# ProPrj_STM32F405RGT6__2024-12-01.net
KiCad netlist of a schematic drawn in EasyEDA Pro
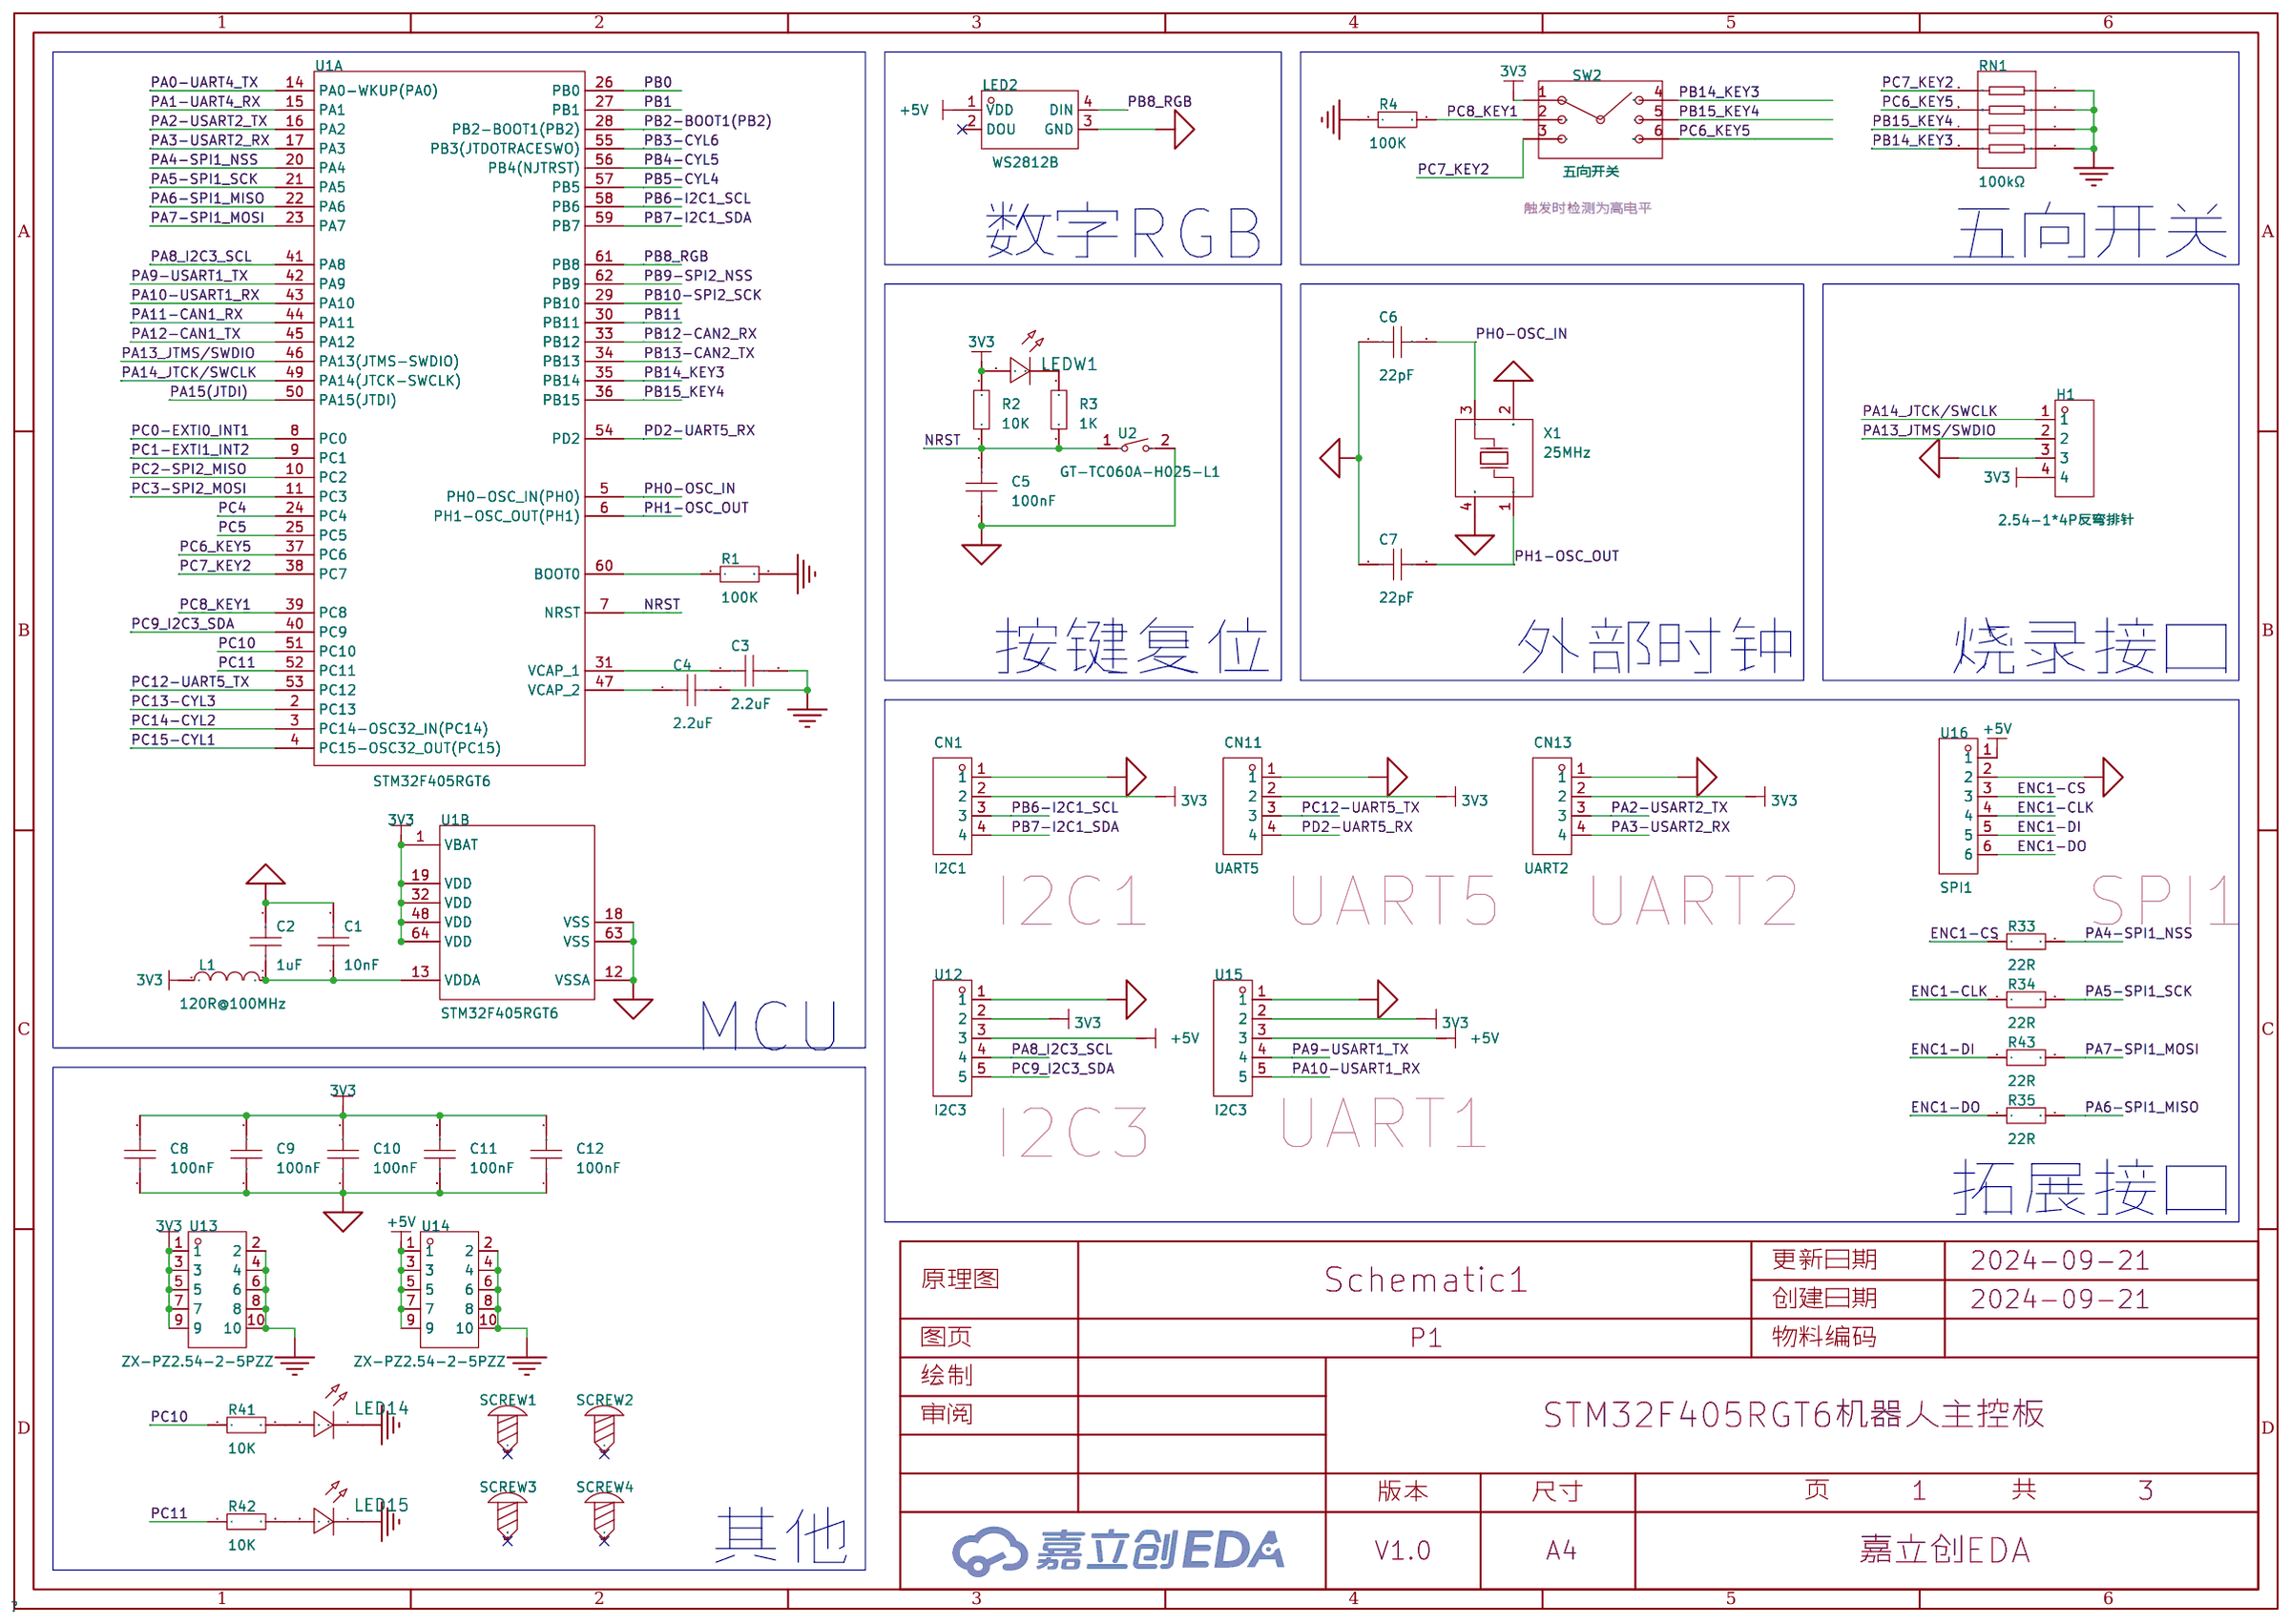
[diagram p0: P1]
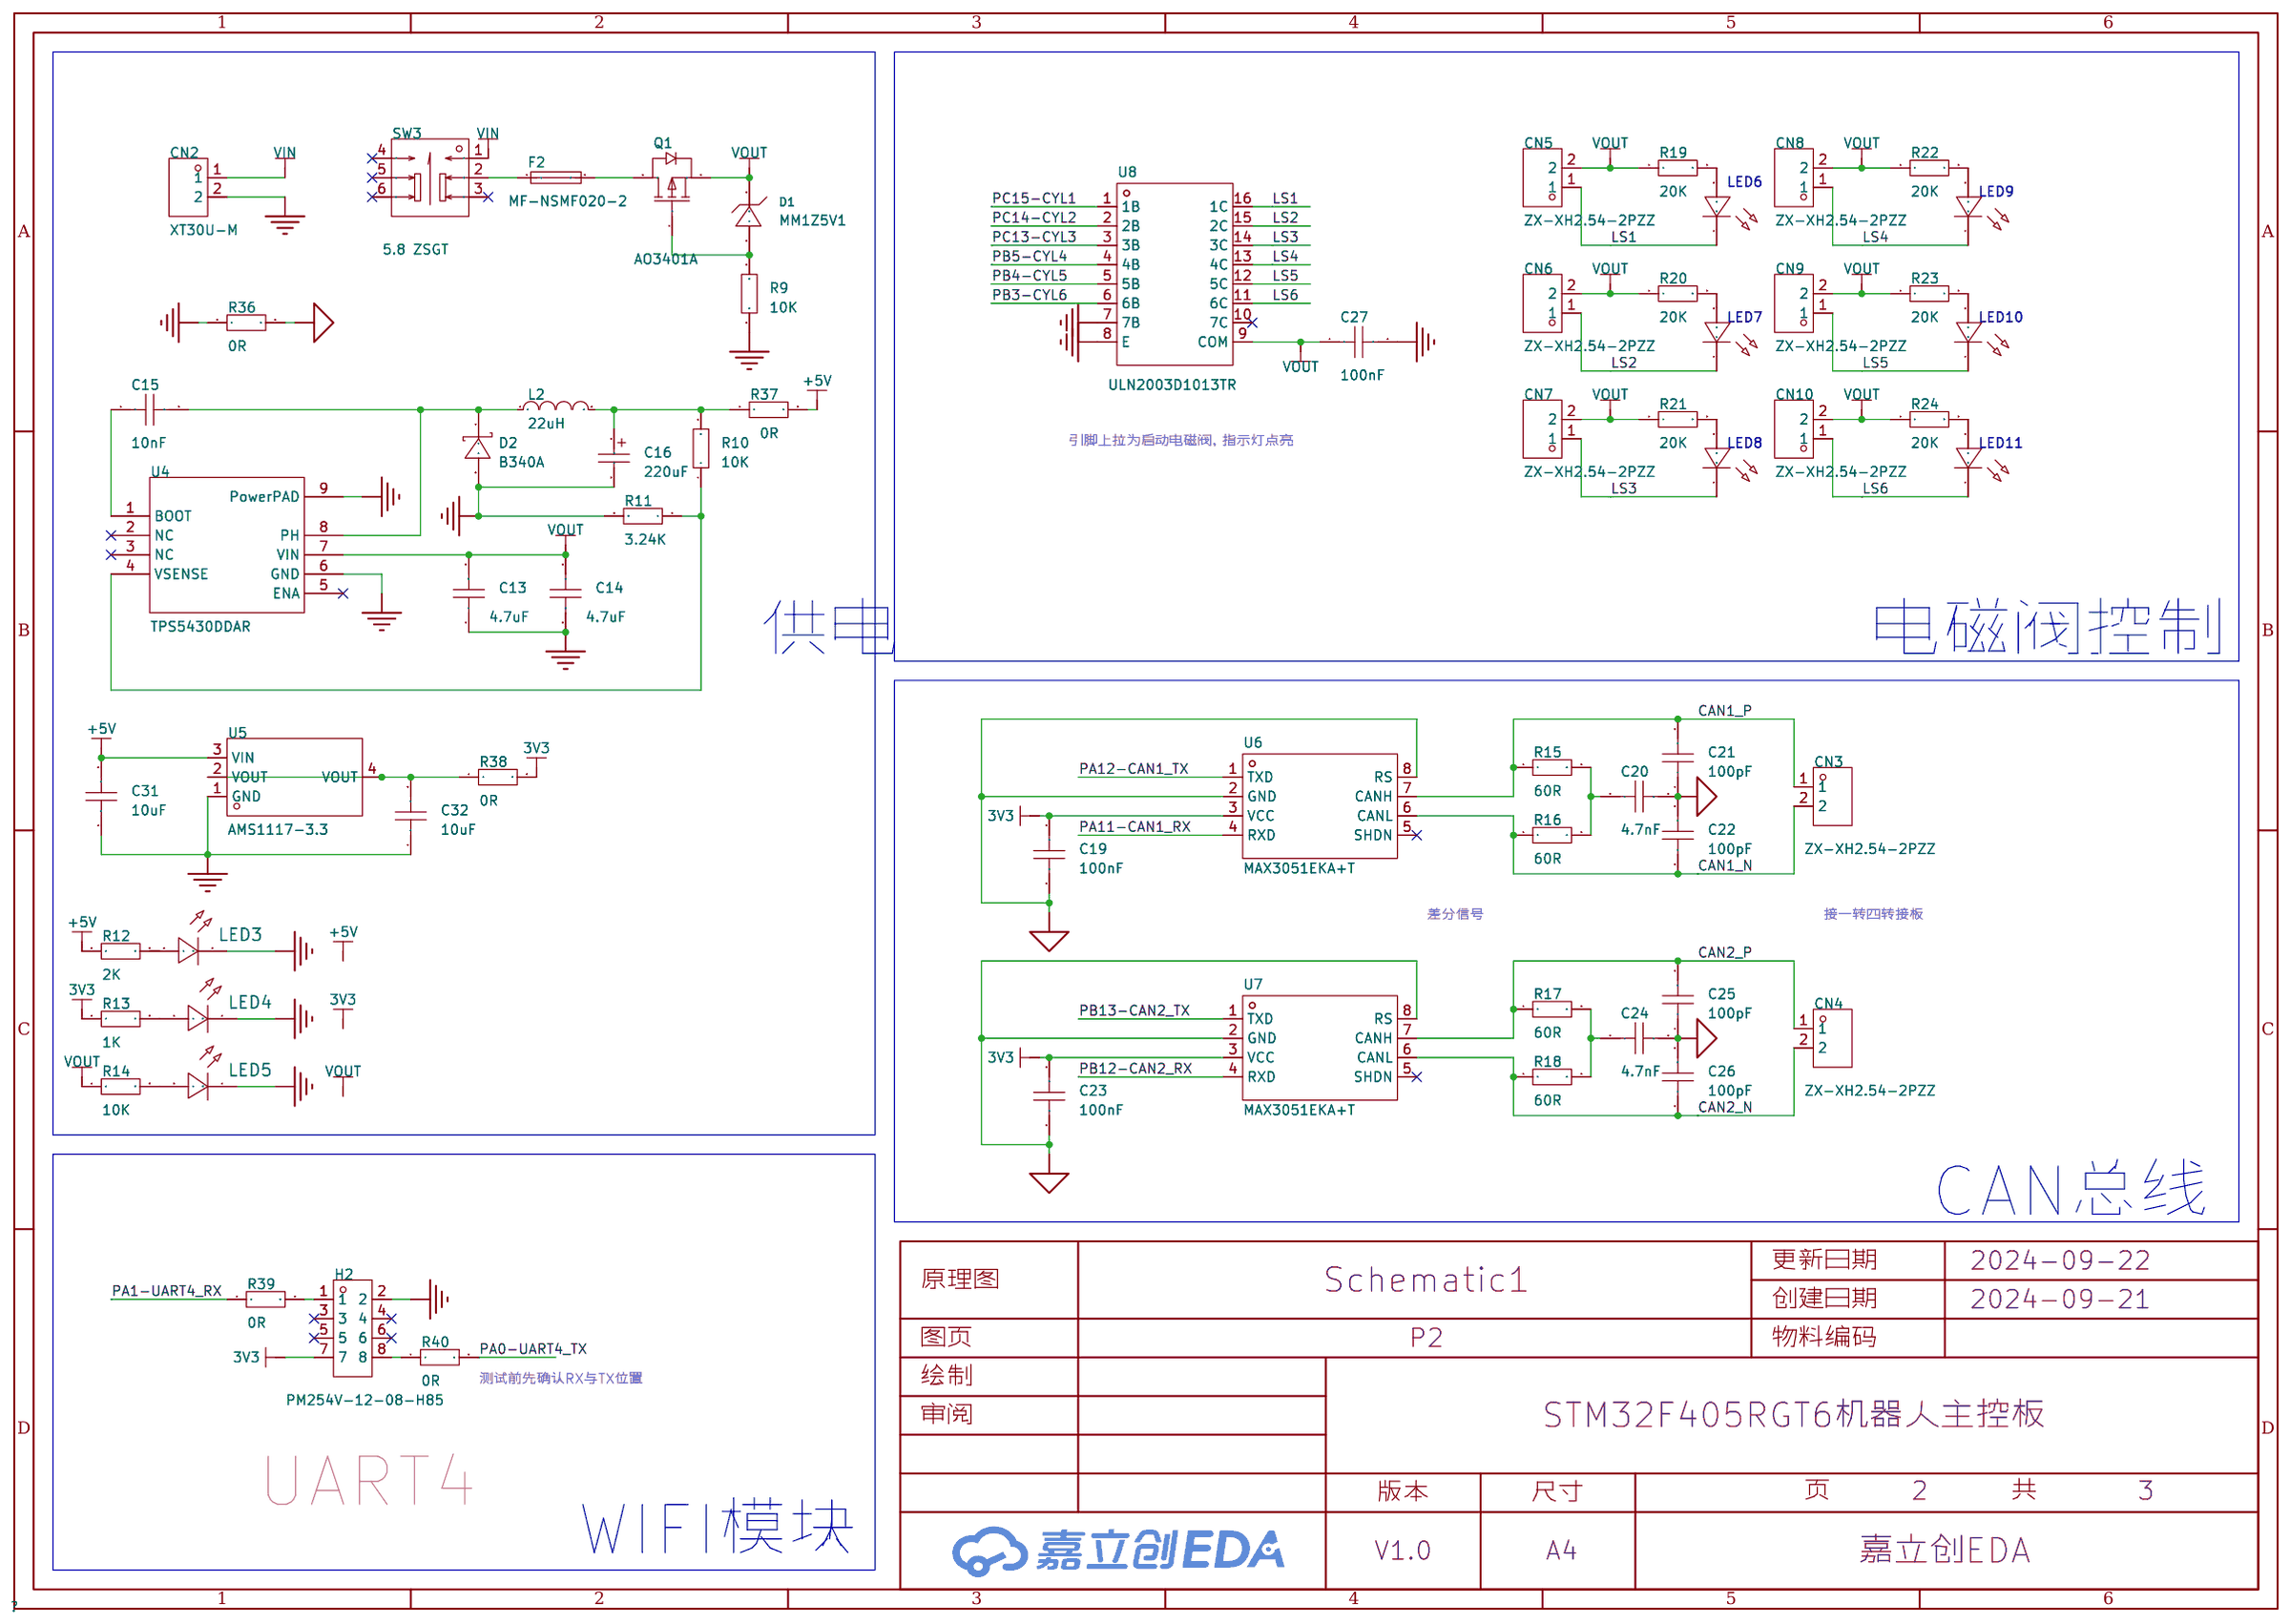
[diagram p1: P2]
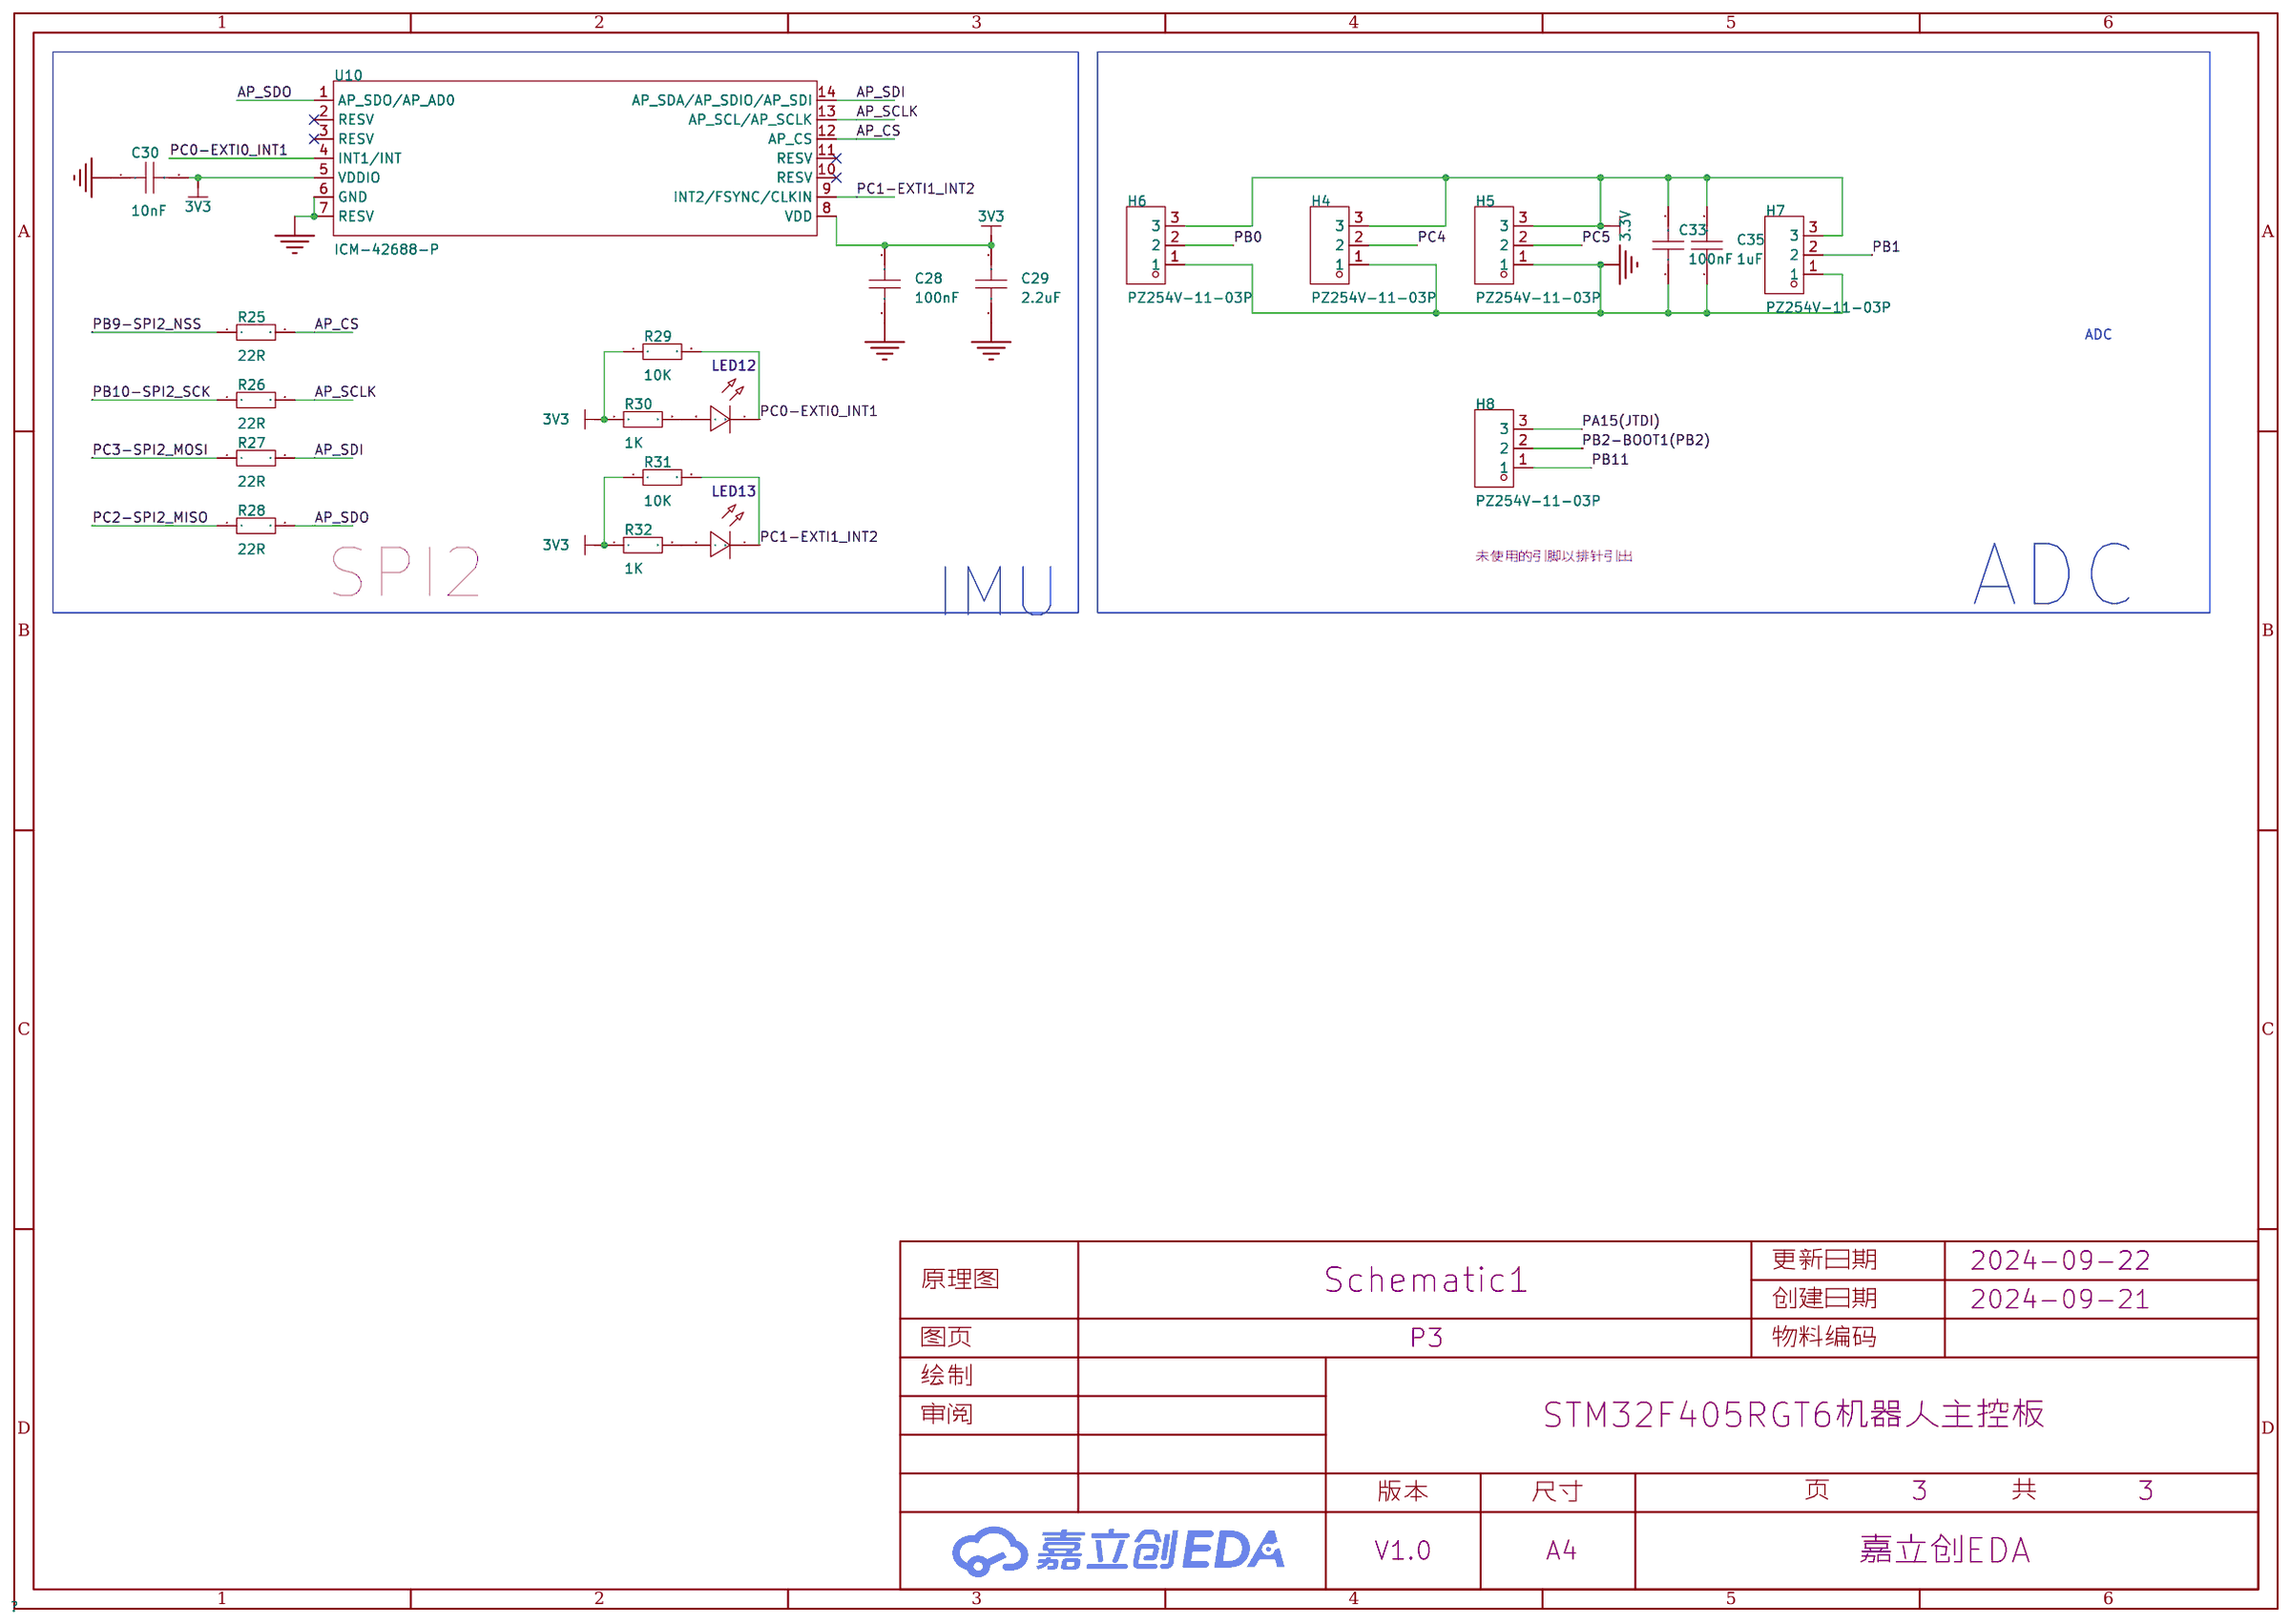
[diagram p2: P3]

(export (version "E")
  (design (tool "Eeschema 10.0.6"))
  (components
    (comp (ref "C1")
      (value "10nF")
      (footprint "easyedapro:C1206")
      (libsource (lib "easyedapro") (part "CapAcitance"))
    )
    (comp (ref "C2")
      (value "1uF")
      (footprint "easyedapro:C1206")
      (libsource (lib "easyedapro") (part "CapAcitance"))
    )
    (comp (ref "C3")
      (value "2.2uF")
      (footprint "easyedapro:C1206")
      (libsource (lib "easyedapro") (part "CapAcitance"))
    )
    (comp (ref "C4")
      (value "2.2uF")
      (footprint "easyedapro:C1206")
      (libsource (lib "easyedapro") (part "CapAcitance"))
    )
    (comp (ref "C5")
      (value "100nF")
      (footprint "easyedapro:C1206")
      (libsource (lib "easyedapro") (part "CapAcitance"))
    )
    (comp (ref "C6")
      (value "22pF")
      (footprint "easyedapro:C1206")
      (libsource (lib "easyedapro") (part "CapAcitance"))
    )
    (comp (ref "C7")
      (value "22pF")
      (footprint "easyedapro:C1206")
      (libsource (lib "easyedapro") (part "CapAcitance"))
    )
    (comp (ref "C8")
      (value "100nF")
      (footprint "easyedapro:C1206")
      (libsource (lib "easyedapro") (part "CapAcitance"))
    )
    (comp (ref "C9")
      (value "100nF")
      (footprint "easyedapro:C1206")
      (libsource (lib "easyedapro") (part "CapAcitance"))
    )
    (comp (ref "C10")
      (value "100nF")
      (footprint "easyedapro:C1206")
      (libsource (lib "easyedapro") (part "CapAcitance"))
    )
    (comp (ref "C11")
      (value "100nF")
      (footprint "easyedapro:C1206")
      (libsource (lib "easyedapro") (part "CapAcitance"))
    )
    (comp (ref "C12")
      (value "100nF")
      (footprint "easyedapro:C1206")
      (libsource (lib "easyedapro") (part "CapAcitance"))
    )
    (comp (ref "CN1")
      (value "I2C1")
      (footprint "easyedapro:CONN-TH_4P-P2.50_4PIN")
      (fields (field (name "Manufacturer") "Megastar(兆星)"))
      (libsource (lib "easyedapro") (part "ZX-XH2.54-4PZZ"))
    )
    (comp (ref "CN11")
      (value "UART5")
      (footprint "easyedapro:CONN-TH_4P-P2.50_4PIN")
      (fields (field (name "Manufacturer") "Megastar(兆星)"))
      (libsource (lib "easyedapro") (part "ZX-XH2.54-4PZZ"))
    )
    (comp (ref "CN13")
      (value "UART2")
      (footprint "easyedapro:CONN-TH_4P-P2.50_4PIN")
      (fields (field (name "Manufacturer") "Megastar(兆星)"))
      (libsource (lib "easyedapro") (part "ZX-XH2.54-4PZZ"))
    )
    (comp (ref "H1")
      (value "2.54-1*4P反弯排针")
      (footprint "easyedapro:HDR-TH_4P-P2.54-H-M-W10.4")
      (fields (field (name "Manufacturer") "BOOMELE(博穆精密)"))
      (libsource (lib "easyedapro") (part "2.54-1*4P反弯排针"))
    )
    (comp (ref "L1")
      (value "120R@100MHz")
      (footprint "easyedapro:L0603")
      (description "标称阻抗@测试频率:120Ω@100MHz;误差:±25%;直流电阻(RDC):50mΩ;")
      (fields (field (name "Manufacturer") "muRata(村田)"))
      (libsource (lib "easyedapro") (part "BLM18PG121SN1D_C14709"))
    )
    (comp (ref "LED2")
      (value "WS2812B")
      (footprint "easyedapro:LED-SMD_4P-L5.0-W5.0-BL_XL-5050RGBC")
      (description "5050七彩幻彩透明贴片LED灯珠 5050 幻彩透明四脚 ws2812B 内置驱动IC")
      (fields (field (name "Manufacturer") "XINGLIGHT(成兴光)"))
      (libsource (lib "easyedapro") (part "XL-5050RGBC-WS2812B"))
    )
    (comp (ref "LED14")
      (value "~")
      (footprint "easyedapro:LED_0603")
      (libsource (lib "easyedapro") (part "LED_R"))
    )
    (comp (ref "LED15")
      (value "~")
      (footprint "easyedapro:LED_0603")
      (libsource (lib "easyedapro") (part "LED_R"))
    )
    (comp (ref "LEDW1")
      (value "~")
      (footprint "easyedapro:LED_0603")
      (libsource (lib "easyedapro") (part "LED_R"))
    )
    (comp (ref "R1") (value "100K") (footprint "easyedapro:R0603") (libsource (lib "easyedapro") (part "电阻")))
    (comp (ref "R2") (value "10K") (footprint "easyedapro:R0603") (libsource (lib "easyedapro") (part "电阻")))
    (comp (ref "R3") (value "1K") (footprint "easyedapro:R0603") (libsource (lib "easyedapro") (part "电阻")))
    (comp (ref "R4") (value "100K") (footprint "easyedapro:R0603") (libsource (lib "easyedapro") (part "电阻")))
    (comp (ref "R33") (value "22R") (footprint "easyedapro:R0603") (libsource (lib "easyedapro") (part "电阻")))
    (comp (ref "R34") (value "22R") (footprint "easyedapro:R0603") (libsource (lib "easyedapro") (part "电阻")))
    (comp (ref "R35") (value "22R") (footprint "easyedapro:R0603") (libsource (lib "easyedapro") (part "电阻")))
    (comp (ref "R41") (value "10K") (footprint "easyedapro:R0603") (libsource (lib "easyedapro") (part "电阻")))
    (comp (ref "R42") (value "10K") (footprint "easyedapro:R0603") (libsource (lib "easyedapro") (part "电阻")))
    (comp (ref "R43") (value "22R") (footprint "easyedapro:R0603") (libsource (lib "easyedapro") (part "电阻")))
    (comp (ref "RN1")
      (value "100kΩ")
      (footprint "easyedapro:RES-ARRAY-SMD_0603-8P-L3.2-W1.6-BL")
      (description "电阻器数:4;阻值:100kΩ;精度:±1%;单个元件功率:62.5mW;温度系数:±200ppm/°C;")
      (fields
        (field (name "Manufacturer Part") "4D03WGF1003T5E")
        (field (name "Manufacturer") "UNI-ROYAL(厚声)")
      )
      (libsource (lib "easyedapro") (part "4D03WGF1003T5E"))
    )
    (comp (ref "SCREW1")
      (value "~")
      (footprint "easyedapro:M3螺丝")
      (libsource (lib "easyedapro") (part "螺丝孔"))
    )
    (comp (ref "SCREW2")
      (value "~")
      (footprint "easyedapro:M3螺丝")
      (libsource (lib "easyedapro") (part "螺丝孔"))
    )
    (comp (ref "SCREW3")
      (value "~")
      (footprint "easyedapro:M3螺丝")
      (libsource (lib "easyedapro") (part "螺丝孔"))
    )
    (comp (ref "SCREW4")
      (value "~")
      (footprint "easyedapro:M3螺丝")
      (libsource (lib "easyedapro") (part "螺丝孔"))
    )
    (comp (ref "SW2")
      (value "五向开关")
      (footprint "easyedapro:SW-SMD_K1-1504SA-06")
      (fields (field (name "Manufacturer") "韩国韩荣"))
      (libsource (lib "easyedapro") (part "K1-1504SA-06"))
    )
    (comp (ref "U1")
      (value "STM32F405RGT6")
      (footprint "easyedapro:LQFP-64_L10.0-W10.0-P0.50-LS12.0-BL")
      (description "CPU内核:ARM-M4;程序存储容量:1MB;RAM总容量:192KB;GPIO端口数量:51;工作电压范围:1.8V~3.6V;CPU最大主频:168MHz;程序存储器类型:FLASH;")
      (fields (field (name "Manufacturer") "ST(意法半导体)"))
      (libsource (lib "easyedapro") (part "STM32F405RGT6"))
    )
    (comp (ref "U2")
      (value "GT-TC060A-H025-L1")
      (footprint "easyedapro:SW-SMD_L6.1-W3.5-LS8.0")
      (fields (field (name "Manufacturer") "G-Switch(品赞)"))
      (libsource (lib "easyedapro") (part "GT-TC060A-H025-L1"))
    )
    (comp (ref "U12")
      (value "I2C3")
      (footprint "easyedapro:CONN-TH_5P-P2.50_ZX-XH2.54-5PZZ")
      (fields (field (name "Manufacturer") "Megastar(兆星)"))
      (libsource (lib "easyedapro") (part "ZX-XH2.54-5PZZ"))
    )
    (comp (ref "U13")
      (value "ZX-PZ2.54-2-5PZZ")
      (footprint "easyedapro:HDR-TH_10P-P2.54-V-M-R2-C5-S2.54")
      (fields (field (name "Manufacturer") "Megastar(兆星)"))
      (libsource (lib "easyedapro") (part "ZX-PZ2.54-2-5PZZ"))
    )
    (comp (ref "U14")
      (value "ZX-PZ2.54-2-5PZZ")
      (footprint "easyedapro:HDR-TH_10P-P2.54-V-M-R2-C5-S2.54")
      (fields (field (name "Manufacturer") "Megastar(兆星)"))
      (libsource (lib "easyedapro") (part "ZX-PZ2.54-2-5PZZ"))
    )
    (comp (ref "U15")
      (value "I2C3")
      (footprint "easyedapro:CONN-TH_5P-P2.50_ZX-XH2.54-5PZZ")
      (fields (field (name "Manufacturer") "Megastar(兆星)"))
      (libsource (lib "easyedapro") (part "ZX-XH2.54-5PZZ"))
    )
    (comp (ref "U16")
      (value "SPI1")
      (footprint "easyedapro:CONN-TH_6P-P2.50_ZX-XH2.54-6PZZ")
      (fields (field (name "Manufacturer") "Megastar(兆星)"))
      (libsource (lib "easyedapro") (part "ZX-XH2.54-6PZZ"))
    )
    (comp (ref "X1")
      (value "25MHz")
      (footprint "easyedapro:OSC-SMD_4P-L3.2-W2.5-BL")
      (description "晶振类型:贴片晶振;频率:25MHz;常温频差:±10ppm;外接负载电容:20pF;频率稳定度(全温):±20ppm;")
      (fields (field (name "Manufacturer Part") "X322525MSB4SI") (field (name "Manufacturer") "YXC(扬兴晶振)"))
      (libsource (lib "easyedapro") (part "X322525MSB4SI"))
    )
    (comp (ref "C13")
      (value "4.7uF")
      (footprint "easyedapro:C1206")
      (libsource (lib "easyedapro") (part "CapAcitance"))
    )
    (comp (ref "C14")
      (value "4.7uF")
      (footprint "easyedapro:C1206")
      (libsource (lib "easyedapro") (part "CapAcitance"))
    )
    (comp (ref "C15")
      (value "10nF")
      (footprint "easyedapro:C1206")
      (libsource (lib "easyedapro") (part "CapAcitance"))
    )
    (comp (ref "C16")
      (value "220uF")
      (footprint "easyedapro:CASE-B_3528")
      (description "容值:220uF;精度:±20%;额定电压:6.3V;等效串联电阻:500mΩ@100kHz;")
      (fields
        (field (name "Manufacturer Part") "TLJB227M006R0500")
        (field (name "Manufacturer") "Kyocera AVX")
      )
      (libsource (lib "easyedapro") (part "TLJB227M006R0500"))
    )
    (comp (ref "C19")
      (value "100nF")
      (footprint "easyedapro:C1206")
      (libsource (lib "easyedapro") (part "CapAcitance"))
    )
    (comp (ref "C20")
      (value "4.7nF")
      (footprint "easyedapro:C1206")
      (libsource (lib "easyedapro") (part "CapAcitance"))
    )
    (comp (ref "C21")
      (value "100pF")
      (footprint "easyedapro:C1206")
      (libsource (lib "easyedapro") (part "CapAcitance"))
    )
    (comp (ref "C22")
      (value "100pF")
      (footprint "easyedapro:C1206")
      (libsource (lib "easyedapro") (part "CapAcitance"))
    )
    (comp (ref "C23")
      (value "100nF")
      (footprint "easyedapro:C1206")
      (libsource (lib "easyedapro") (part "CapAcitance"))
    )
    (comp (ref "C24")
      (value "4.7nF")
      (footprint "easyedapro:C1206")
      (libsource (lib "easyedapro") (part "CapAcitance"))
    )
    (comp (ref "C25")
      (value "100pF")
      (footprint "easyedapro:C1206")
      (libsource (lib "easyedapro") (part "CapAcitance"))
    )
    (comp (ref "C26")
      (value "100pF")
      (footprint "easyedapro:C1206")
      (libsource (lib "easyedapro") (part "CapAcitance"))
    )
    (comp (ref "C27")
      (value "100nF")
      (footprint "easyedapro:C1206")
      (libsource (lib "easyedapro") (part "CapAcitance"))
    )
    (comp (ref "C31")
      (value "10uF")
      (footprint "easyedapro:C1210")
      (description "容值:10uF;精度:±10%;额定电压:100V;材质(温度系数):X7R;")
      (fields (field (name "Manufacturer Part") "FS32X106K101EGG") (field (name "Manufacturer") "PSA(信昌电陶)"))
      (libsource (lib "easyedapro") (part "FS32X106K101EGG"))
    )
    (comp (ref "C32")
      (value "10uF")
      (footprint "easyedapro:C1210")
      (description "容值:10uF;精度:±10%;额定电压:100V;材质(温度系数):X7R;")
      (fields (field (name "Manufacturer Part") "FS32X106K101EGG") (field (name "Manufacturer") "PSA(信昌电陶)"))
      (libsource (lib "easyedapro") (part "FS32X106K101EGG"))
    )
    (comp (ref "CN2")
      (value "XT30U-M")
      (footprint "easyedapro:CONN-TH_XT30U-M")
      (description "类别:-;类型1:-;")
      (fields (field (name "Manufacturer") "AMASS(艾迈斯)"))
      (libsource (lib "easyedapro") (part "XT30U-M"))
    )
    (comp (ref "CN3")
      (value "ZX-XH2.54-2PZZ")
      (footprint "easyedapro:CONN-TH_2P-P2.50_HX25003-2A")
      (fields (field (name "Manufacturer") "Megastar(兆星)"))
      (libsource (lib "easyedapro") (part "ZX-XH2.54-2PZZ"))
    )
    (comp (ref "CN4")
      (value "ZX-XH2.54-2PZZ")
      (footprint "easyedapro:CONN-TH_2P-P2.50_HX25003-2A")
      (fields (field (name "Manufacturer") "Megastar(兆星)"))
      (libsource (lib "easyedapro") (part "ZX-XH2.54-2PZZ"))
    )
    (comp (ref "CN5")
      (value "ZX-XH2.54-2PZZ")
      (footprint "easyedapro:CONN-TH_2P-P2.50_HX25003-2A")
      (fields (field (name "Manufacturer") "Megastar(兆星)"))
      (libsource (lib "easyedapro") (part "ZX-XH2.54-2PZZ"))
    )
    (comp (ref "CN6")
      (value "ZX-XH2.54-2PZZ")
      (footprint "easyedapro:CONN-TH_2P-P2.50_HX25003-2A")
      (fields (field (name "Manufacturer") "Megastar(兆星)"))
      (libsource (lib "easyedapro") (part "ZX-XH2.54-2PZZ"))
    )
    (comp (ref "CN7")
      (value "ZX-XH2.54-2PZZ")
      (footprint "easyedapro:CONN-TH_2P-P2.50_HX25003-2A")
      (fields (field (name "Manufacturer") "Megastar(兆星)"))
      (libsource (lib "easyedapro") (part "ZX-XH2.54-2PZZ"))
    )
    (comp (ref "CN8")
      (value "ZX-XH2.54-2PZZ")
      (footprint "easyedapro:CONN-TH_2P-P2.50_HX25003-2A")
      (fields (field (name "Manufacturer") "Megastar(兆星)"))
      (libsource (lib "easyedapro") (part "ZX-XH2.54-2PZZ"))
    )
    (comp (ref "CN9")
      (value "ZX-XH2.54-2PZZ")
      (footprint "easyedapro:CONN-TH_2P-P2.50_HX25003-2A")
      (fields (field (name "Manufacturer") "Megastar(兆星)"))
      (libsource (lib "easyedapro") (part "ZX-XH2.54-2PZZ"))
    )
    (comp (ref "CN10")
      (value "ZX-XH2.54-2PZZ")
      (footprint "easyedapro:CONN-TH_2P-P2.50_HX25003-2A")
      (fields (field (name "Manufacturer") "Megastar(兆星)"))
      (libsource (lib "easyedapro") (part "ZX-XH2.54-2PZZ"))
    )
    (comp (ref "D1")
      (value "MM1Z5V1")
      (footprint "easyedapro:SOD-123_L2.8-W1.8-LS3.7-RD")
      (description "二极管配置:独立式;稳压值(标称值):5.1V;稳压值(范围):4.8V~5.4V;功率:500mW;精度:±6%;")
      (fields (field (name "Manufacturer") "晶导微电子"))
      (libsource (lib "easyedapro") (part "MM1Z5V1_C112534"))
    )
    (comp (ref "D2")
      (value "B340A")
      (footprint "easyedapro:SMA_L4.3-W2.6-LS5.1-RD")
      (description "二极管配置:独立式;正向压降(Vf):550mV@3A;直流反向耐压(Vr):40V;整流电流:3A;")
      (fields (field (name "Manufacturer") "MDD(辰达半导体)"))
      (libsource (lib "easyedapro") (part "B340A"))
    )
    (comp (ref "F2")
      (value "MF-NSMF020-2")
      (footprint "easyedapro:F1206")
      (description "最大电压:24V;最大电流:10A;保持电流:200mA;跳闸电流:460mA;")
      (fields (field (name "Manufacturer") "BOURNS"))
      (libsource (lib "easyedapro") (part "MF-NSMF020-2"))
    )
    (comp (ref "H2")
      (value "PM254V-12-08-H85")
      (footprint "easyedapro:HDR-TH_8P-P2.54-V-F-R2-C4-S2.54")
      (fields (field (name "Manufacturer") "XFCN(兴飞)"))
      (libsource (lib "easyedapro") (part "PM254V-12-08-H85_C2834799"))
    )
    (comp (ref "L2")
      (value "22uH")
      (footprint "easyedapro:IND-SMD_L4.0-W4.0_LQH44PN2R2MP0L")
      (description "电感值:22uH;精度:±20%;额定电流:-;饱和电流(Isat):1.05A;")
      (fields (field (name "Manufacturer Part") "SMNR4020-22UH") (field (name "Manufacturer") "SXN(顺翔诺)"))
      (libsource (lib "easyedapro") (part "SMNR4020-22UH"))
    )
    (comp (ref "LED3")
      (value "~")
      (footprint "easyedapro:LED_0603")
      (libsource (lib "easyedapro") (part "LED_R"))
    )
    (comp (ref "LED4")
      (value "~")
      (footprint "easyedapro:LED_0603")
      (libsource (lib "easyedapro") (part "LED_R"))
    )
    (comp (ref "LED5")
      (value "~")
      (footprint "easyedapro:LED_0603")
      (libsource (lib "easyedapro") (part "LED_R"))
    )
    (comp (ref "LED6")
      (value "~")
      (footprint "easyedapro:LED_0603")
      (libsource (lib "easyedapro") (part "LED_B"))
    )
    (comp (ref "LED7")
      (value "~")
      (footprint "easyedapro:LED_0603")
      (libsource (lib "easyedapro") (part "LED_B"))
    )
    (comp (ref "LED8")
      (value "~")
      (footprint "easyedapro:LED_0603")
      (libsource (lib "easyedapro") (part "LED_B"))
    )
    (comp (ref "LED9")
      (value "~")
      (footprint "easyedapro:LED_0603")
      (libsource (lib "easyedapro") (part "LED_B"))
    )
    (comp (ref "LED10")
      (value "~")
      (footprint "easyedapro:LED_0603")
      (libsource (lib "easyedapro") (part "LED_B"))
    )
    (comp (ref "LED11")
      (value "~")
      (footprint "easyedapro:LED_0603")
      (libsource (lib "easyedapro") (part "LED_B"))
    )
    (comp (ref "Q1")
      (value "AO3401A")
      (footprint "easyedapro:SOT-23_L2.9-W1.3-P1.90-LS2.4-BR")
      (fields (field (name "Manufacturer") "AOS"))
      (libsource (lib "easyedapro") (part "AO3401A"))
    )
    (comp (ref "R9") (value "10K") (footprint "easyedapro:R0603") (libsource (lib "easyedapro") (part "电阻")))
    (comp (ref "R10") (value "10K") (footprint "easyedapro:R0603") (libsource (lib "easyedapro") (part "电阻")))
    (comp (ref "R11")
      (value "3.24K")
      (footprint "easyedapro:R0603")
      (libsource (lib "easyedapro") (part "电阻"))
    )
    (comp (ref "R12") (value "2K") (footprint "easyedapro:R0603") (libsource (lib "easyedapro") (part "电阻")))
    (comp (ref "R13") (value "1K") (footprint "easyedapro:R0603") (libsource (lib "easyedapro") (part "电阻")))
    (comp (ref "R14") (value "10K") (footprint "easyedapro:R0603") (libsource (lib "easyedapro") (part "电阻")))
    (comp (ref "R15") (value "60R") (footprint "easyedapro:R0603") (libsource (lib "easyedapro") (part "电阻")))
    (comp (ref "R16") (value "60R") (footprint "easyedapro:R0603") (libsource (lib "easyedapro") (part "电阻")))
    (comp (ref "R17") (value "60R") (footprint "easyedapro:R0603") (libsource (lib "easyedapro") (part "电阻")))
    (comp (ref "R18") (value "60R") (footprint "easyedapro:R0603") (libsource (lib "easyedapro") (part "电阻")))
    (comp (ref "R19") (value "20K") (footprint "easyedapro:R0603") (libsource (lib "easyedapro") (part "电阻")))
    (comp (ref "R20") (value "20K") (footprint "easyedapro:R0603") (libsource (lib "easyedapro") (part "电阻")))
    (comp (ref "R21") (value "20K") (footprint "easyedapro:R0603") (libsource (lib "easyedapro") (part "电阻")))
    (comp (ref "R22") (value "20K") (footprint "easyedapro:R0603") (libsource (lib "easyedapro") (part "电阻")))
    (comp (ref "R23") (value "20K") (footprint "easyedapro:R0603") (libsource (lib "easyedapro") (part "电阻")))
    (comp (ref "R24") (value "20K") (footprint "easyedapro:R0603") (libsource (lib "easyedapro") (part "电阻")))
    (comp (ref "R36") (value "0R") (footprint "easyedapro:R0603") (libsource (lib "easyedapro") (part "电阻")))
    (comp (ref "R37") (value "0R") (footprint "easyedapro:R0603") (libsource (lib "easyedapro") (part "电阻")))
    (comp (ref "R38") (value "0R") (footprint "easyedapro:R0603") (libsource (lib "easyedapro") (part "电阻")))
    (comp (ref "R39") (value "0R") (footprint "easyedapro:R0603") (libsource (lib "easyedapro") (part "电阻")))
    (comp (ref "R40") (value "0R") (footprint "easyedapro:R0603") (libsource (lib "easyedapro") (part "电阻")))
    (comp (ref "SW3")
      (value "5.8 ZSGT")
      (footprint "easyedapro:SW-TH_5.8ZSGT")
      (description "电路结构:双刀双掷;自锁/无锁:自锁;安装方式:直插;触点电流:110mA;额定电压 (DC):30V;带灯:不带;作用力:1.5N;机械寿命:10万次;")
      (fields (field (name "Manufacturer") "SHOU HAN(首韩)"))
      (libsource (lib "easyedapro") (part "5.8 ZSGT"))
    )
    (comp (ref "U4")
      (value "TPS5430DDAR")
      (footprint "easyedapro:ESOP-8_L4.9-W3.9-P1.27-LS6.0-TL-EP")
      (description "功能类型:降压型;输出类型:可调;输入电压:5.5V~36V;输出电压:1.221V~32.04V;输出电流(最大值):3A;")
      (fields (field (name "Manufacturer") "TI(德州仪器)"))
      (libsource (lib "easyedapro") (part "TPS5430DDAR"))
    )
    (comp (ref "U5")
      (value "AMS1117-3.3")
      (footprint "easyedapro:SOT-223-3_L6.5-W3.4-P2.30-LS7.0-BR")
      (description "输出类型:固定;最大输入电压:-;输出电压:3.3V;最大输出电流:1A;电源纹波抑制比(PSRR):72dB@(120Hz);输出极性:正极;")
      (fields (field (name "Manufacturer") "AMS"))
      (libsource (lib "easyedapro") (part "AMS1117-3.3"))
    )
    (comp (ref "U6")
      (value "MAX3051EKA+T")
      (footprint "easyedapro:SOT-23-8_L3.0-W1.7-P0.65-LS2.8-TL")
      (description "类型:收发器;数据速率:1Mbps;")
      (fields (field (name "Manufacturer") "ADI(亚德诺)/MAXIM(美信)"))
      (libsource (lib "easyedapro") (part "MAX3051EKA+T"))
    )
    (comp (ref "U7")
      (value "MAX3051EKA+T")
      (footprint "easyedapro:SOT-23-8_L3.0-W1.7-P0.65-LS2.8-TL")
      (description "类型:收发器;数据速率:1Mbps;")
      (fields (field (name "Manufacturer") "ADI(亚德诺)/MAXIM(美信)"))
      (libsource (lib "easyedapro") (part "MAX3051EKA+T"))
    )
    (comp (ref "U8")
      (value "ULN2003D1013TR")
      (footprint "easyedapro:SOIC-16_L9.9-W3.9-P1.27-LS6.0-BL")
      (description "通道数:七路;集射击穿电压(Vceo):50V;")
      (fields (field (name "Manufacturer") "ST(意法半导体)"))
      (libsource (lib "easyedapro") (part "ULN2003D1013TR"))
    )
    (comp (ref "C28")
      (value "100nF")
      (footprint "easyedapro:C1206")
      (libsource (lib "easyedapro") (part "CapAcitance"))
    )
    (comp (ref "C29")
      (value "2.2uF")
      (footprint "easyedapro:C1206")
      (libsource (lib "easyedapro") (part "CapAcitance"))
    )
    (comp (ref "C30")
      (value "10nF")
      (footprint "easyedapro:C1206")
      (libsource (lib "easyedapro") (part "CapAcitance"))
    )
    (comp (ref "C33")
      (value "100nF")
      (footprint "easyedapro:C0805")
      (description "容值:100nF;精度:±10%;额定电压:50V;材质(温度系数):X7R;")
      (fields
        (field (name "Manufacturer Part") "CC0805KRX7R9BB104")
        (field (name "Manufacturer") "YAGEO(国巨)")
      )
      (libsource (lib "easyedapro") (part "CC0805KRX7R9BB104"))
    )
    (comp (ref "C35")
      (value "1uF")
      (footprint "easyedapro:C0603")
      (description "容值:1uF;精度:±10%;额定电压:50V;材质(温度系数):X5R;")
      (fields
        (field (name "Manufacturer Part") "CL10A105KB8NNNC")
        (field (name "Manufacturer") "SAMSUNG(三星)")
      )
      (libsource (lib "easyedapro") (part "CL10A105KB8NNNC"))
    )
    (comp (ref "H4")
      (value "PZ254V-11-03P")
      (footprint "easyedapro:HDR-TH_3P-P2.54-V-M")
      (fields (field (name "Manufacturer") "XFCN(兴飞)"))
      (libsource (lib "easyedapro") (part "PZ254V-11-03P_C2937625"))
    )
    (comp (ref "H5")
      (value "PZ254V-11-03P")
      (footprint "easyedapro:HDR-TH_3P-P2.54-V-M")
      (fields (field (name "Manufacturer") "XFCN(兴飞)"))
      (libsource (lib "easyedapro") (part "PZ254V-11-03P_C2937625"))
    )
    (comp (ref "H6")
      (value "PZ254V-11-03P")
      (footprint "easyedapro:HDR-TH_3P-P2.54-V-M")
      (fields (field (name "Manufacturer") "XFCN(兴飞)"))
      (libsource (lib "easyedapro") (part "PZ254V-11-03P_C2937625"))
    )
    (comp (ref "H7")
      (value "PZ254V-11-03P")
      (footprint "easyedapro:HDR-TH_3P-P2.54-V-M")
      (fields (field (name "Manufacturer") "XFCN(兴飞)"))
      (libsource (lib "easyedapro") (part "PZ254V-11-03P_C2937625"))
    )
    (comp (ref "H8")
      (value "PZ254V-11-03P")
      (footprint "easyedapro:HDR-TH_3P-P2.54-V-M")
      (fields (field (name "Manufacturer") "XFCN(兴飞)"))
      (libsource (lib "easyedapro") (part "PZ254V-11-03P_C2937625"))
    )
    (comp (ref "LED12")
      (value "~")
      (footprint "easyedapro:LED_0603")
      (libsource (lib "easyedapro") (part "LED_B"))
    )
    (comp (ref "LED13")
      (value "~")
      (footprint "easyedapro:LED_0603")
      (libsource (lib "easyedapro") (part "LED_G"))
    )
    (comp (ref "R25") (value "22R") (footprint "easyedapro:R0603") (libsource (lib "easyedapro") (part "电阻")))
    (comp (ref "R26") (value "22R") (footprint "easyedapro:R0603") (libsource (lib "easyedapro") (part "电阻")))
    (comp (ref "R27") (value "22R") (footprint "easyedapro:R0603") (libsource (lib "easyedapro") (part "电阻")))
    (comp (ref "R28") (value "22R") (footprint "easyedapro:R0603") (libsource (lib "easyedapro") (part "电阻")))
    (comp (ref "R29") (value "10K") (footprint "easyedapro:R0603") (libsource (lib "easyedapro") (part "电阻")))
    (comp (ref "R30") (value "1K") (footprint "easyedapro:R0603") (libsource (lib "easyedapro") (part "电阻")))
    (comp (ref "R31") (value "10K") (footprint "easyedapro:R0603") (libsource (lib "easyedapro") (part "电阻")))
    (comp (ref "R32") (value "1K") (footprint "easyedapro:R0603") (libsource (lib "easyedapro") (part "电阻")))
    (comp (ref "U10")
      (value "ICM-42688-P")
      (footprint "easyedapro:LGA-14_L3.0-W2.5-P0.50-TL")
      (description "传感器类型:加速度计陀螺仪;")
      (fields (field (name "Manufacturer") "TDK InvenSense(应美盛)"))
      (libsource (lib "easyedapro") (part "ICM-42688-P"))
    )
  )
  (nets
    (net (code "1") (name "+5V") (class "Default")
      (node (ref "C31") (pin "2") (pinfunction "2_2") (pintype "unspecified"))
      (node (ref "LED2") (pin "1") (pinfunction "VDD_1") (pintype "unspecified"))
      (node (ref "R12") (pin "1") (pinfunction "1_1") (pintype "input"))
      (node (ref "R37") (pin "2") (pinfunction "2_2") (pintype "input"))
      (node (ref "U12") (pin "3") (pinfunction "3_3") (pintype "unspecified"))
      (node (ref "U14") (pin "1") (pinfunction "1_1") (pintype "unspecified"))
      (node (ref "U14") (pin "3") (pinfunction "3_3") (pintype "unspecified"))
      (node (ref "U14") (pin "5") (pinfunction "5_5") (pintype "unspecified"))
      (node (ref "U14") (pin "7") (pinfunction "7_7") (pintype "unspecified"))
      (node (ref "U14") (pin "9") (pinfunction "9_9") (pintype "unspecified"))
      (node (ref "U15") (pin "3") (pinfunction "3_3") (pintype "unspecified"))
      (node (ref "U16") (pin "1") (pinfunction "1_1") (pintype "unspecified"))
      (node (ref "U5") (pin "3") (pinfunction "VIN_3") (pintype "unspecified"))
    )
    (net (code "2") (name "3.3V") (class "Default")
      (node (ref "C33") (pin "2") (pinfunction "2_2") (pintype "unspecified"))
      (node (ref "C35") (pin "2") (pinfunction "2_2") (pintype "unspecified"))
      (node (ref "H4") (pin "3") (pinfunction "3_3") (pintype "unspecified"))
      (node (ref "H5") (pin "3") (pinfunction "3_3") (pintype "unspecified"))
      (node (ref "H6") (pin "3") (pinfunction "3_3") (pintype "unspecified"))
      (node (ref "H7") (pin "3") (pinfunction "3_3") (pintype "unspecified"))
    )
    (net (code "3") (name "3V3") (class "Default")
      (node (ref "C10") (pin "2") (pinfunction "2_2") (pintype "input"))
      (node (ref "C11") (pin "2") (pinfunction "2_2") (pintype "input"))
      (node (ref "C12") (pin "2") (pinfunction "2_2") (pintype "input"))
      (node (ref "C19") (pin "2") (pinfunction "2_2") (pintype "input"))
      (node (ref "C23") (pin "2") (pinfunction "2_2") (pintype "input"))
      (node (ref "C28") (pin "2") (pinfunction "2_2") (pintype "input"))
      (node (ref "C29") (pin "2") (pinfunction "2_2") (pintype "input"))
      (node (ref "C30") (pin "2") (pinfunction "2_2") (pintype "input"))
      (node (ref "C8") (pin "2") (pinfunction "2_2") (pintype "input"))
      (node (ref "C9") (pin "2") (pinfunction "2_2") (pintype "input"))
      (node (ref "CN1") (pin "2") (pinfunction "2_2") (pintype "unspecified"))
      (node (ref "CN11") (pin "2") (pinfunction "2_2") (pintype "unspecified"))
      (node (ref "CN13") (pin "2") (pinfunction "2_2") (pintype "unspecified"))
      (node (ref "H1") (pin "4") (pinfunction "4_4") (pintype "unspecified"))
      (node (ref "H2") (pin "7") (pinfunction "7_7") (pintype "unspecified"))
      (node (ref "L1") (pin "1") (pinfunction "1_1") (pintype "unspecified"))
      (node (ref "LEDW1") (pin "2") (pinfunction "A_2") (pintype "input"))
      (node (ref "R13") (pin "1") (pinfunction "1_1") (pintype "input"))
      (node (ref "R2") (pin "2") (pinfunction "2_2") (pintype "input"))
      (node (ref "R29") (pin "1") (pinfunction "1_1") (pintype "input"))
      (node (ref "R30") (pin "1") (pinfunction "1_1") (pintype "input"))
      (node (ref "R31") (pin "1") (pinfunction "1_1") (pintype "input"))
      (node (ref "R32") (pin "1") (pinfunction "1_1") (pintype "input"))
      (node (ref "R38") (pin "2") (pinfunction "2_2") (pintype "input"))
      (node (ref "SW2") (pin "1") (pinfunction "A_1") (pintype "unspecified"))
      (node (ref "U1") (pin "1") (pinfunction "VBAT_1") (pintype "unspecified"))
      (node (ref "U1") (pin "19") (pinfunction "VDD_19") (pintype "unspecified"))
      (node (ref "U1") (pin "32") (pinfunction "VDD_32") (pintype "unspecified"))
      (node (ref "U1") (pin "48") (pinfunction "VDD_48") (pintype "unspecified"))
      (node (ref "U1") (pin "64") (pinfunction "VDD_64") (pintype "unspecified"))
      (node (ref "U10") (pin "5") (pinfunction "VDDIO_5") (pintype "unspecified"))
      (node (ref "U10") (pin "8") (pinfunction "VDD_8") (pintype "unspecified"))
      (node (ref "U12") (pin "2") (pinfunction "2_2") (pintype "unspecified"))
      (node (ref "U13") (pin "1") (pinfunction "1_1") (pintype "unspecified"))
      (node (ref "U13") (pin "3") (pinfunction "3_3") (pintype "unspecified"))
      (node (ref "U13") (pin "5") (pinfunction "5_5") (pintype "unspecified"))
      (node (ref "U13") (pin "7") (pinfunction "7_7") (pintype "unspecified"))
      (node (ref "U13") (pin "9") (pinfunction "9_9") (pintype "unspecified"))
      (node (ref "U15") (pin "2") (pinfunction "2_2") (pintype "unspecified"))
      (node (ref "U6") (pin "3") (pinfunction "VCC_3") (pintype "unspecified"))
      (node (ref "U7") (pin "3") (pinfunction "VCC_3") (pintype "unspecified"))
    )
    (net (code "4") (name "AGND") (class "Default")
      (node (ref "C1") (pin "2") (pinfunction "2_2") (pintype "input"))
      (node (ref "C10") (pin "1") (pinfunction "1_1") (pintype "input"))
      (node (ref "C11") (pin "1") (pinfunction "1_1") (pintype "input"))
      (node (ref "C12") (pin "1") (pinfunction "1_1") (pintype "input"))
      (node (ref "C19") (pin "1") (pinfunction "1_1") (pintype "input"))
      (node (ref "C2") (pin "2") (pinfunction "2_2") (pintype "input"))
      (node (ref "C20") (pin "2") (pinfunction "2_2") (pintype "input"))
      (node (ref "C21") (pin "1") (pinfunction "1_1") (pintype "input"))
      (node (ref "C22") (pin "2") (pinfunction "2_2") (pintype "input"))
      (node (ref "C23") (pin "1") (pinfunction "1_1") (pintype "input"))
      (node (ref "C24") (pin "2") (pinfunction "2_2") (pintype "input"))
      (node (ref "C25") (pin "1") (pinfunction "1_1") (pintype "input"))
      (node (ref "C26") (pin "2") (pinfunction "2_2") (pintype "input"))
      (node (ref "C5") (pin "1") (pinfunction "1_1") (pintype "input"))
      (node (ref "C6") (pin "1") (pinfunction "1_1") (pintype "input"))
      (node (ref "C7") (pin "1") (pinfunction "1_1") (pintype "input"))
      (node (ref "C8") (pin "1") (pinfunction "1_1") (pintype "input"))
      (node (ref "C9") (pin "1") (pinfunction "1_1") (pintype "input"))
      (node (ref "CN1") (pin "1") (pinfunction "1_1") (pintype "unspecified"))
      (node (ref "CN11") (pin "1") (pinfunction "1_1") (pintype "unspecified"))
      (node (ref "CN13") (pin "1") (pinfunction "1_1") (pintype "unspecified"))
      (node (ref "H1") (pin "3") (pinfunction "3_3") (pintype "unspecified"))
      (node (ref "LED2") (pin "3") (pinfunction "GND_3") (pintype "unspecified"))
      (node (ref "R36") (pin "2") (pinfunction "2_2") (pintype "input"))
      (node (ref "U1") (pin "12") (pinfunction "VSSA_12") (pintype "unspecified"))
      (node (ref "U1") (pin "18") (pinfunction "VSS_18") (pintype "unspecified"))
      (node (ref "U1") (pin "63") (pinfunction "VSS_63") (pintype "unspecified"))
      (node (ref "U12") (pin "1") (pinfunction "1_1") (pintype "unspecified"))
      (node (ref "U15") (pin "1") (pinfunction "1_1") (pintype "unspecified"))
      (node (ref "U16") (pin "2") (pinfunction "2_2") (pintype "unspecified"))
      (node (ref "U2") (pin "2") (pinfunction "2_2") (pintype "unspecified"))
      (node (ref "U6") (pin "2") (pinfunction "GND_2") (pintype "unspecified"))
      (node (ref "U6") (pin "8") (pinfunction "RS_8") (pintype "unspecified"))
      (node (ref "U7") (pin "2") (pinfunction "GND_2") (pintype "unspecified"))
      (node (ref "U7") (pin "8") (pinfunction "RS_8") (pintype "unspecified"))
      (node (ref "X1") (pin "2") (pinfunction "GND_2") (pintype "unspecified"))
      (node (ref "X1") (pin "4") (pinfunction "GND_4") (pintype "unspecified"))
    )
    (net (code "5") (name "AP_CS") (class "Default")
      (node (ref "R25") (pin "2") (pinfunction "2_2") (pintype "input"))
      (node (ref "U10") (pin "12") (pinfunction "AP_CS_12") (pintype "unspecified"))
    )
    (net (code "6") (name "AP_SCLK") (class "Default")
      (node (ref "R26") (pin "2") (pinfunction "2_2") (pintype "input"))
      (node (ref "U10") (pin "13") (pinfunction "AP_SCL/AP_SCLK_13") (pintype "unspecified"))
    )
    (net (code "7") (name "AP_SDI") (class "Default")
      (node (ref "R27") (pin "2") (pinfunction "2_2") (pintype "input"))
      (node (ref "U10") (pin "14") (pinfunction "AP_SDA/AP_SDIO/AP_SDI_14") (pintype "unspecified"))
    )
    (net (code "8") (name "AP_SDO") (class "Default")
      (node (ref "R28") (pin "2") (pinfunction "2_2") (pintype "input"))
      (node (ref "U10") (pin "1") (pinfunction "AP_SDO/AP_AD0_1") (pintype "unspecified"))
    )
    (net (code "9") (name "CAN1_N") (class "Default")
      (node (ref "C22") (pin "1") (pinfunction "1_1") (pintype "input"))
      (node (ref "CN3") (pin "2") (pinfunction "2_2") (pintype "unspecified"))
      (node (ref "R16") (pin "1") (pinfunction "1_1") (pintype "input"))
      (node (ref "U6") (pin "6") (pinfunction "CANL_6") (pintype "unspecified"))
    )
    (net (code "10") (name "CAN1_P") (class "Default")
      (node (ref "C21") (pin "2") (pinfunction "2_2") (pintype "input"))
      (node (ref "CN3") (pin "1") (pinfunction "1_1") (pintype "unspecified"))
      (node (ref "R15") (pin "1") (pinfunction "1_1") (pintype "input"))
      (node (ref "U6") (pin "7") (pinfunction "CANH_7") (pintype "unspecified"))
    )
    (net (code "11") (name "CAN2_N") (class "Default")
      (node (ref "C26") (pin "1") (pinfunction "1_1") (pintype "input"))
      (node (ref "CN4") (pin "2") (pinfunction "2_2") (pintype "unspecified"))
      (node (ref "R18") (pin "1") (pinfunction "1_1") (pintype "input"))
      (node (ref "U7") (pin "6") (pinfunction "CANL_6") (pintype "unspecified"))
    )
    (net (code "12") (name "CAN2_P") (class "Default")
      (node (ref "C25") (pin "2") (pinfunction "2_2") (pintype "input"))
      (node (ref "CN4") (pin "1") (pinfunction "1_1") (pintype "unspecified"))
      (node (ref "R17") (pin "1") (pinfunction "1_1") (pintype "input"))
      (node (ref "U7") (pin "7") (pinfunction "CANH_7") (pintype "unspecified"))
    )
    (net (code "13") (name "ENC1-CLK") (class "Default")
      (node (ref "R34") (pin "1") (pinfunction "1_1") (pintype "input"))
      (node (ref "U16") (pin "4") (pinfunction "4_4") (pintype "unspecified"))
    )
    (net (code "14") (name "ENC1-CS") (class "Default")
      (node (ref "R33") (pin "1") (pinfunction "1_1") (pintype "input"))
      (node (ref "U16") (pin "3") (pinfunction "3_3") (pintype "unspecified"))
    )
    (net (code "15") (name "ENC1-DI") (class "Default")
      (node (ref "R43") (pin "1") (pinfunction "1_1") (pintype "input"))
      (node (ref "U16") (pin "5") (pinfunction "5_5") (pintype "unspecified"))
    )
    (net (code "16") (name "ENC1-DO") (class "Default")
      (node (ref "R35") (pin "1") (pinfunction "1_1") (pintype "input"))
      (node (ref "U16") (pin "6") (pinfunction "6_6") (pintype "unspecified"))
    )
    (net (code "17") (name "GND") (class "Default")
      (node (ref "C13") (pin "1") (pinfunction "1_1") (pintype "input"))
      (node (ref "C14") (pin "1") (pinfunction "1_1") (pintype "input"))
      (node (ref "C16") (pin "2") (pinfunction "2_2") (pintype "input"))
      (node (ref "C27") (pin "2") (pinfunction "2_2") (pintype "input"))
      (node (ref "C28") (pin "1") (pinfunction "1_1") (pintype "input"))
      (node (ref "C29") (pin "1") (pinfunction "1_1") (pintype "input"))
      (node (ref "C3") (pin "2") (pinfunction "2_2") (pintype "input"))
      (node (ref "C30") (pin "1") (pinfunction "1_1") (pintype "input"))
      (node (ref "C31") (pin "1") (pinfunction "1_1") (pintype "unspecified"))
      (node (ref "C32") (pin "1") (pinfunction "1_1") (pintype "unspecified"))
      (node (ref "C33") (pin "1") (pinfunction "1_1") (pintype "unspecified"))
      (node (ref "C35") (pin "1") (pinfunction "1_1") (pintype "unspecified"))
      (node (ref "C4") (pin "2") (pinfunction "2_2") (pintype "input"))
      (node (ref "CN2") (pin "2") (pinfunction "2_2") (pintype "unspecified"))
      (node (ref "D2") (pin "2") (pinfunction "A_2") (pintype "unspecified"))
      (node (ref "H2") (pin "2") (pinfunction "2_2") (pintype "unspecified"))
      (node (ref "H4") (pin "1") (pinfunction "1_1") (pintype "unspecified"))
      (node (ref "H5") (pin "1") (pinfunction "1_1") (pintype "unspecified"))
      (node (ref "H6") (pin "1") (pinfunction "1_1") (pintype "unspecified"))
      (node (ref "H7") (pin "1") (pinfunction "1_1") (pintype "unspecified"))
      (node (ref "LED14") (pin "1") (pinfunction "C_1") (pintype "input"))
      (node (ref "LED15") (pin "1") (pinfunction "C_1") (pintype "input"))
      (node (ref "LED3") (pin "1") (pinfunction "C_1") (pintype "input"))
      (node (ref "LED4") (pin "1") (pinfunction "C_1") (pintype "input"))
      (node (ref "LED5") (pin "1") (pinfunction "C_1") (pintype "input"))
      (node (ref "R1") (pin "2") (pinfunction "2_2") (pintype "input"))
      (node (ref "R11") (pin "2") (pinfunction "2_2") (pintype "input"))
      (node (ref "R36") (pin "1") (pinfunction "1_1") (pintype "input"))
      (node (ref "R4") (pin "1") (pinfunction "1_1") (pintype "input"))
      (node (ref "R9") (pin "1") (pinfunction "1_1") (pintype "input"))
      (node (ref "RN1") (pin "1") (pinfunction "1_1") (pintype "input"))
      (node (ref "RN1") (pin "2") (pinfunction "2_2") (pintype "input"))
      (node (ref "RN1") (pin "3") (pinfunction "3_3") (pintype "input"))
      (node (ref "RN1") (pin "4") (pinfunction "4_4") (pintype "input"))
      (node (ref "U10") (pin "6") (pinfunction "GND_6") (pintype "unspecified"))
      (node (ref "U10") (pin "7") (pinfunction "RESV_7") (pintype "unspecified"))
      (node (ref "U13") (pin "10") (pinfunction "10_10") (pintype "unspecified"))
      (node (ref "U13") (pin "2") (pinfunction "2_2") (pintype "unspecified"))
      (node (ref "U13") (pin "4") (pinfunction "4_4") (pintype "unspecified"))
      (node (ref "U13") (pin "6") (pinfunction "6_6") (pintype "unspecified"))
      (node (ref "U13") (pin "8") (pinfunction "8_8") (pintype "unspecified"))
      (node (ref "U14") (pin "10") (pinfunction "10_10") (pintype "unspecified"))
      (node (ref "U14") (pin "2") (pinfunction "2_2") (pintype "unspecified"))
      (node (ref "U14") (pin "4") (pinfunction "4_4") (pintype "unspecified"))
      (node (ref "U14") (pin "6") (pinfunction "6_6") (pintype "unspecified"))
      (node (ref "U14") (pin "8") (pinfunction "8_8") (pintype "unspecified"))
      (node (ref "U4") (pin "6") (pinfunction "GND_6") (pintype "unspecified"))
      (node (ref "U4") (pin "9") (pinfunction "PowerPAD_9") (pintype "unspecified"))
      (node (ref "U5") (pin "1") (pinfunction "GND_1") (pintype "unspecified"))
      (node (ref "U8") (pin "7") (pinfunction "7B_7") (pintype "unspecified"))
      (node (ref "U8") (pin "8") (pinfunction "E_8") (pintype "unspecified"))
    )
    (net (code "18") (name "LS1") (class "Default")
      (node (ref "CN5") (pin "1") (pinfunction "1_1") (pintype "unspecified"))
      (node (ref "LED6") (pin "1") (pinfunction "C_1") (pintype "input"))
      (node (ref "U8") (pin "16") (pinfunction "1C_16") (pintype "unspecified"))
    )
    (net (code "19") (name "LS2") (class "Default")
      (node (ref "CN6") (pin "1") (pinfunction "1_1") (pintype "unspecified"))
      (node (ref "LED7") (pin "1") (pinfunction "C_1") (pintype "input"))
      (node (ref "U8") (pin "15") (pinfunction "2C_15") (pintype "unspecified"))
    )
    (net (code "20") (name "LS3") (class "Default")
      (node (ref "CN7") (pin "1") (pinfunction "1_1") (pintype "unspecified"))
      (node (ref "LED8") (pin "1") (pinfunction "C_1") (pintype "input"))
      (node (ref "U8") (pin "14") (pinfunction "3C_14") (pintype "unspecified"))
    )
    (net (code "21") (name "LS4") (class "Default")
      (node (ref "CN8") (pin "1") (pinfunction "1_1") (pintype "unspecified"))
      (node (ref "LED9") (pin "1") (pinfunction "C_1") (pintype "input"))
      (node (ref "U8") (pin "13") (pinfunction "4C_13") (pintype "unspecified"))
    )
    (net (code "22") (name "LS5") (class "Default")
      (node (ref "CN9") (pin "1") (pinfunction "1_1") (pintype "unspecified"))
      (node (ref "LED10") (pin "1") (pinfunction "C_1") (pintype "input"))
      (node (ref "U8") (pin "12") (pinfunction "5C_12") (pintype "unspecified"))
    )
    (net (code "23") (name "LS6") (class "Default")
      (node (ref "CN10") (pin "1") (pinfunction "1_1") (pintype "unspecified"))
      (node (ref "LED11") (pin "1") (pinfunction "C_1") (pintype "input"))
      (node (ref "U8") (pin "11") (pinfunction "6C_11") (pintype "unspecified"))
    )
    (net (code "24") (name "NRST") (class "Default")
      (node (ref "C5") (pin "2") (pinfunction "2_2") (pintype "input"))
      (node (ref "R2") (pin "1") (pinfunction "1_1") (pintype "input"))
      (node (ref "R3") (pin "1") (pinfunction "1_1") (pintype "input"))
      (node (ref "U1") (pin "7") (pinfunction "NRST_7") (pintype "bidirectional"))
      (node (ref "U2") (pin "1") (pinfunction "1_1") (pintype "unspecified"))
    )
    (net (code "25") (name "Net-(C16-Pad1)") (class "Default")
      (node (ref "C16") (pin "1") (pinfunction "1_1") (pintype "input"))
      (node (ref "L2") (pin "2") (pinfunction "2_2") (pintype "unspecified"))
      (node (ref "R10") (pin "2") (pinfunction "2_2") (pintype "input"))
      (node (ref "R37") (pin "1") (pinfunction "1_1") (pintype "input"))
    )
    (net (code "26") (name "Net-(C20-Pad1)") (class "Default")
      (node (ref "C20") (pin "1") (pinfunction "1_1") (pintype "input"))
      (node (ref "R15") (pin "2") (pinfunction "2_2") (pintype "input"))
      (node (ref "R16") (pin "2") (pinfunction "2_2") (pintype "input"))
    )
    (net (code "27") (name "Net-(C24-Pad1)") (class "Default")
      (node (ref "C24") (pin "1") (pinfunction "1_1") (pintype "input"))
      (node (ref "R17") (pin "2") (pinfunction "2_2") (pintype "input"))
      (node (ref "R18") (pin "2") (pinfunction "2_2") (pintype "input"))
    )
    (net (code "28") (name "Net-(C32-Pad2)") (class "Default")
      (node (ref "C32") (pin "2") (pinfunction "2_2") (pintype "unspecified"))
      (node (ref "R38") (pin "1") (pinfunction "1_1") (pintype "input"))
      (node (ref "U5") (pin "2") (pinfunction "VOUT_2") (pintype "unspecified"))
      (node (ref "U5") (pin "4") (pinfunction "VOUT_4") (pintype "unspecified"))
    )
    (net (code "29") (name "Net-(D1-A)") (class "Default")
      (node (ref "D1") (pin "2") (pinfunction "A_2") (pintype "input"))
      (node (ref "Q1") (pin "1") (pinfunction "G_1") (pintype "unspecified"))
      (node (ref "R9") (pin "2") (pinfunction "2_2") (pintype "input"))
    )
    (net (code "30") (name "Net-(D2-K)") (class "Default")
      (node (ref "C15") (pin "2") (pinfunction "2_2") (pintype "input"))
      (node (ref "D2") (pin "1") (pinfunction "K_1") (pintype "unspecified"))
      (node (ref "L2") (pin "1") (pinfunction "1_1") (pintype "unspecified"))
      (node (ref "U4") (pin "8") (pinfunction "PH_8") (pintype "unspecified"))
    )
    (net (code "31") (name "Net-(F2-Pad1)") (class "Default")
      (node (ref "F2") (pin "1") (pinfunction "1_1") (pintype "unspecified"))
      (node (ref "SW3") (pin "2") (pinfunction "2_2") (pintype "unspecified"))
    )
    (net (code "32") (name "Net-(H2-Pad1)") (class "Default")
      (node (ref "H2") (pin "1") (pinfunction "1_1") (pintype "unspecified"))
      (node (ref "R39") (pin "2") (pinfunction "2_2") (pintype "input"))
    )
    (net (code "33") (name "Net-(H2-Pad8)") (class "Default")
      (node (ref "H2") (pin "8") (pinfunction "8_8") (pintype "unspecified"))
      (node (ref "R40") (pin "1") (pinfunction "1_1") (pintype "input"))
    )
    (net (code "34") (name "Net-(LED3-A)") (class "Default")
      (node (ref "LED3") (pin "2") (pinfunction "A_2") (pintype "input"))
      (node (ref "R12") (pin "2") (pinfunction "2_2") (pintype "input"))
    )
    (net (code "35") (name "Net-(LED4-A)") (class "Default")
      (node (ref "LED4") (pin "2") (pinfunction "A_2") (pintype "input"))
      (node (ref "R13") (pin "2") (pinfunction "2_2") (pintype "input"))
    )
    (net (code "36") (name "Net-(LED5-A)") (class "Default")
      (node (ref "LED5") (pin "2") (pinfunction "A_2") (pintype "input"))
      (node (ref "R14") (pin "2") (pinfunction "2_2") (pintype "input"))
    )
    (net (code "37") (name "Net-(LED6-A)") (class "Default")
      (node (ref "LED6") (pin "2") (pinfunction "A_2") (pintype "input"))
      (node (ref "R19") (pin "2") (pinfunction "2_2") (pintype "input"))
    )
    (net (code "38") (name "Net-(LED7-A)") (class "Default")
      (node (ref "LED7") (pin "2") (pinfunction "A_2") (pintype "input"))
      (node (ref "R20") (pin "2") (pinfunction "2_2") (pintype "input"))
    )
    (net (code "39") (name "Net-(LED8-A)") (class "Default")
      (node (ref "LED8") (pin "2") (pinfunction "A_2") (pintype "input"))
      (node (ref "R21") (pin "2") (pinfunction "2_2") (pintype "input"))
    )
    (net (code "40") (name "Net-(LED9-A)") (class "Default")
      (node (ref "LED9") (pin "2") (pinfunction "A_2") (pintype "input"))
      (node (ref "R22") (pin "2") (pinfunction "2_2") (pintype "input"))
    )
    (net (code "41") (name "Net-(LED10-A)") (class "Default")
      (node (ref "LED10") (pin "2") (pinfunction "A_2") (pintype "input"))
      (node (ref "R23") (pin "2") (pinfunction "2_2") (pintype "input"))
    )
    (net (code "42") (name "Net-(LED11-A)") (class "Default")
      (node (ref "LED11") (pin "2") (pinfunction "A_2") (pintype "input"))
      (node (ref "R24") (pin "2") (pinfunction "2_2") (pintype "input"))
    )
    (net (code "43") (name "Net-(LED12-A)") (class "Default")
      (node (ref "LED12") (pin "2") (pinfunction "A_2") (pintype "input"))
      (node (ref "R30") (pin "2") (pinfunction "2_2") (pintype "input"))
    )
    (net (code "44") (name "Net-(LED13-A)") (class "Default")
      (node (ref "LED13") (pin "2") (pinfunction "A_2") (pintype "input"))
      (node (ref "R32") (pin "2") (pinfunction "2_2") (pintype "input"))
    )
    (net (code "45") (name "Net-(LED14-A)") (class "Default")
      (node (ref "LED14") (pin "2") (pinfunction "A_2") (pintype "input"))
      (node (ref "R41") (pin "2") (pinfunction "2_2") (pintype "input"))
    )
    (net (code "46") (name "Net-(LED15-A)") (class "Default")
      (node (ref "LED15") (pin "2") (pinfunction "A_2") (pintype "input"))
      (node (ref "R42") (pin "2") (pinfunction "2_2") (pintype "input"))
    )
    (net (code "47") (name "Net-(LEDW1-C)") (class "Default")
      (node (ref "LEDW1") (pin "1") (pinfunction "C_1") (pintype "input"))
      (node (ref "R3") (pin "2") (pinfunction "2_2") (pintype "input"))
    )
    (net (code "48") (name "Net-(Q1-D)") (class "Default")
      (node (ref "F2") (pin "2") (pinfunction "2_2") (pintype "unspecified"))
      (node (ref "Q1") (pin "3") (pinfunction "D_3") (pintype "unspecified"))
    )
    (net (code "49") (name "Net-(U1A-BOOT0)") (class "Default")
      (node (ref "R1") (pin "1") (pinfunction "1_1") (pintype "input"))
      (node (ref "U1") (pin "60") (pinfunction "BOOT0_60") (pintype "unspecified"))
    )
    (net (code "50") (name "Net-(U1A-VCAP_1)") (class "Default")
      (node (ref "C3") (pin "1") (pinfunction "1_1") (pintype "input"))
      (node (ref "U1") (pin "31") (pinfunction "VCAP_1_31") (pintype "unspecified"))
    )
    (net (code "51") (name "Net-(U1A-VCAP_2)") (class "Default")
      (node (ref "C4") (pin "1") (pinfunction "1_1") (pintype "input"))
      (node (ref "U1") (pin "47") (pinfunction "VCAP_2_47") (pintype "unspecified"))
    )
    (net (code "52") (name "Net-(U1B-VDDA)") (class "Default")
      (node (ref "C1") (pin "1") (pinfunction "1_1") (pintype "input"))
      (node (ref "C2") (pin "1") (pinfunction "1_1") (pintype "input"))
      (node (ref "L1") (pin "2") (pinfunction "2_2") (pintype "unspecified"))
      (node (ref "U1") (pin "13") (pinfunction "VDDA_13") (pintype "unspecified"))
    )
    (net (code "53") (name "Net-(U4-BOOT)") (class "Default")
      (node (ref "C15") (pin "1") (pinfunction "1_1") (pintype "input"))
      (node (ref "U4") (pin "1") (pinfunction "BOOT_1") (pintype "unspecified"))
    )
    (net (code "54") (name "Net-(U4-VSENSE)") (class "Default")
      (node (ref "R10") (pin "1") (pinfunction "1_1") (pintype "input"))
      (node (ref "R11") (pin "1") (pinfunction "1_1") (pintype "input"))
      (node (ref "U4") (pin "4") (pinfunction "VSENSE_4") (pintype "unspecified"))
    )
    (net (code "55") (name "PA0-UART4_TX") (class "Default")
      (node (ref "R40") (pin "2") (pinfunction "2_2") (pintype "input"))
      (node (ref "U1") (pin "14") (pinfunction "PA0-WKUP(PA0)_14") (pintype "bidirectional"))
    )
    (net (code "56") (name "PA1-UART4_RX") (class "Default")
      (node (ref "R39") (pin "1") (pinfunction "1_1") (pintype "input"))
      (node (ref "U1") (pin "15") (pinfunction "PA1_15") (pintype "bidirectional"))
    )
    (net (code "57") (name "PA2-USART2_TX") (class "Default")
      (node (ref "CN13") (pin "3") (pinfunction "3_3") (pintype "unspecified"))
      (node (ref "U1") (pin "16") (pinfunction "PA2_16") (pintype "bidirectional"))
    )
    (net (code "58") (name "PA3-USART2_RX") (class "Default")
      (node (ref "CN13") (pin "4") (pinfunction "4_4") (pintype "unspecified"))
      (node (ref "U1") (pin "17") (pinfunction "PA3_17") (pintype "bidirectional"))
    )
    (net (code "59") (name "PA4-SPI1_NSS") (class "Default")
      (node (ref "R33") (pin "2") (pinfunction "2_2") (pintype "input"))
      (node (ref "U1") (pin "20") (pinfunction "PA4_20") (pintype "bidirectional"))
    )
    (net (code "60") (name "PA5-SPI1_SCK") (class "Default")
      (node (ref "R34") (pin "2") (pinfunction "2_2") (pintype "input"))
      (node (ref "U1") (pin "21") (pinfunction "PA5_21") (pintype "bidirectional"))
    )
    (net (code "61") (name "PA6-SPI1_MISO") (class "Default")
      (node (ref "R35") (pin "2") (pinfunction "2_2") (pintype "input"))
      (node (ref "U1") (pin "22") (pinfunction "PA6_22") (pintype "bidirectional"))
    )
    (net (code "62") (name "PA7-SPI1_MOSI") (class "Default")
      (node (ref "R43") (pin "2") (pinfunction "2_2") (pintype "input"))
      (node (ref "U1") (pin "23") (pinfunction "PA7_23") (pintype "bidirectional"))
    )
    (net (code "63") (name "PA8_I2C3_SCL") (class "Default")
      (node (ref "U1") (pin "41") (pinfunction "PA8_41") (pintype "bidirectional"))
      (node (ref "U12") (pin "4") (pinfunction "4_4") (pintype "unspecified"))
    )
    (net (code "64") (name "PA9-USART1_TX") (class "Default")
      (node (ref "U1") (pin "42") (pinfunction "PA9_42") (pintype "bidirectional"))
      (node (ref "U15") (pin "4") (pinfunction "4_4") (pintype "unspecified"))
    )
    (net (code "65") (name "PA10-USART1_RX") (class "Default")
      (node (ref "U1") (pin "43") (pinfunction "PA10_43") (pintype "bidirectional"))
      (node (ref "U15") (pin "5") (pinfunction "5_5") (pintype "unspecified"))
    )
    (net (code "66") (name "PA11-CAN1_RX") (class "Default")
      (node (ref "U1") (pin "44") (pinfunction "PA11_44") (pintype "bidirectional"))
      (node (ref "U6") (pin "4") (pinfunction "RXD_4") (pintype "unspecified"))
    )
    (net (code "67") (name "PA12-CAN1_TX") (class "Default")
      (node (ref "U1") (pin "45") (pinfunction "PA12_45") (pintype "bidirectional"))
      (node (ref "U6") (pin "1") (pinfunction "TXD_1") (pintype "unspecified"))
    )
    (net (code "68") (name "PA13_JTMS{slash}SWDIO") (class "Default")
      (node (ref "H1") (pin "2") (pinfunction "2_2") (pintype "unspecified"))
      (node (ref "U1") (pin "46") (pinfunction "PA13(JTMS-SWDIO)_46") (pintype "bidirectional"))
    )
    (net (code "69") (name "PA14_JTCK{slash}SWCLK") (class "Default")
      (node (ref "H1") (pin "1") (pinfunction "1_1") (pintype "unspecified"))
      (node (ref "U1") (pin "49") (pinfunction "PA14(JTCK-SWCLK)_49") (pintype "bidirectional"))
    )
    (net (code "70") (name "PA15(JTDI)") (class "Default")
      (node (ref "H8") (pin "3") (pinfunction "3_3") (pintype "unspecified"))
      (node (ref "U1") (pin "50") (pinfunction "PA15(JTDI)_50") (pintype "bidirectional"))
    )
    (net (code "71") (name "PB0") (class "Default")
      (node (ref "H6") (pin "2") (pinfunction "2_2") (pintype "unspecified"))
      (node (ref "U1") (pin "26") (pinfunction "PB0_26") (pintype "bidirectional"))
    )
    (net (code "72") (name "PB1") (class "Default")
      (node (ref "H7") (pin "2") (pinfunction "2_2") (pintype "unspecified"))
      (node (ref "U1") (pin "27") (pinfunction "PB1_27") (pintype "bidirectional"))
    )
    (net (code "73") (name "PB2-BOOT1(PB2)") (class "Default")
      (node (ref "H8") (pin "2") (pinfunction "2_2") (pintype "unspecified"))
      (node (ref "U1") (pin "28") (pinfunction "PB2-BOOT1(PB2)_28") (pintype "bidirectional"))
    )
    (net (code "74") (name "PB3-CYL6") (class "Default")
      (node (ref "U1") (pin "55") (pinfunction "PB3(JTDOTRACESWO)_55") (pintype "bidirectional"))
      (node (ref "U8") (pin "6") (pinfunction "6B_6") (pintype "unspecified"))
    )
    (net (code "75") (name "PB4-CYL5") (class "Default")
      (node (ref "U1") (pin "56") (pinfunction "PB4(NJTRST)_56") (pintype "bidirectional"))
      (node (ref "U8") (pin "5") (pinfunction "5B_5") (pintype "unspecified"))
    )
    (net (code "76") (name "PB5-CYL4") (class "Default")
      (node (ref "U1") (pin "57") (pinfunction "PB5_57") (pintype "bidirectional"))
      (node (ref "U8") (pin "4") (pinfunction "4B_4") (pintype "unspecified"))
    )
    (net (code "77") (name "PB6-I2C1_SCL") (class "Default")
      (node (ref "CN1") (pin "3") (pinfunction "3_3") (pintype "unspecified"))
      (node (ref "U1") (pin "58") (pinfunction "PB6_58") (pintype "bidirectional"))
    )
    (net (code "78") (name "PB7-I2C1_SDA") (class "Default")
      (node (ref "CN1") (pin "4") (pinfunction "4_4") (pintype "unspecified"))
      (node (ref "U1") (pin "59") (pinfunction "PB7_59") (pintype "bidirectional"))
    )
    (net (code "79") (name "PB8_RGB") (class "Default")
      (node (ref "LED2") (pin "4") (pinfunction "DIN_4") (pintype "unspecified"))
      (node (ref "U1") (pin "61") (pinfunction "PB8_61") (pintype "bidirectional"))
    )
    (net (code "80") (name "PB9-SPI2_NSS") (class "Default")
      (node (ref "R25") (pin "1") (pinfunction "1_1") (pintype "input"))
      (node (ref "U1") (pin "62") (pinfunction "PB9_62") (pintype "bidirectional"))
    )
    (net (code "81") (name "PB10-SPI2_SCK") (class "Default")
      (node (ref "R26") (pin "1") (pinfunction "1_1") (pintype "input"))
      (node (ref "U1") (pin "29") (pinfunction "PB10_29") (pintype "bidirectional"))
    )
    (net (code "82") (name "PB11") (class "Default")
      (node (ref "H8") (pin "1") (pinfunction "1_1") (pintype "unspecified"))
      (node (ref "U1") (pin "30") (pinfunction "PB11_30") (pintype "bidirectional"))
    )
    (net (code "83") (name "PB12-CAN2_RX") (class "Default")
      (node (ref "U1") (pin "33") (pinfunction "PB12_33") (pintype "bidirectional"))
      (node (ref "U7") (pin "4") (pinfunction "RXD_4") (pintype "unspecified"))
    )
    (net (code "84") (name "PB13-CAN2_TX") (class "Default")
      (node (ref "U1") (pin "34") (pinfunction "PB13_34") (pintype "bidirectional"))
      (node (ref "U7") (pin "1") (pinfunction "TXD_1") (pintype "unspecified"))
    )
    (net (code "85") (name "PB14_KEY3") (class "Default")
      (node (ref "RN1") (pin "8") (pinfunction "8_8") (pintype "input"))
      (node (ref "SW2") (pin "4") (pinfunction "CENTER_4") (pintype "unspecified"))
      (node (ref "U1") (pin "35") (pinfunction "PB14_35") (pintype "bidirectional"))
    )
    (net (code "86") (name "PB15_KEY4") (class "Default")
      (node (ref "RN1") (pin "7") (pinfunction "7_7") (pintype "input"))
      (node (ref "SW2") (pin "5") (pinfunction "D_5") (pintype "unspecified"))
      (node (ref "U1") (pin "36") (pinfunction "PB15_36") (pintype "bidirectional"))
    )
    (net (code "87") (name "PC0-EXTI0_INT1") (class "Default")
      (node (ref "LED12") (pin "1") (pinfunction "C_1") (pintype "input"))
      (node (ref "R29") (pin "2") (pinfunction "2_2") (pintype "input"))
      (node (ref "U1") (pin "8") (pinfunction "PC0_8") (pintype "bidirectional"))
      (node (ref "U10") (pin "4") (pinfunction "INT1/INT_4") (pintype "unspecified"))
    )
    (net (code "88") (name "PC1-EXTI1_INT2") (class "Default")
      (node (ref "LED13") (pin "1") (pinfunction "C_1") (pintype "input"))
      (node (ref "R31") (pin "2") (pinfunction "2_2") (pintype "input"))
      (node (ref "U1") (pin "9") (pinfunction "PC1_9") (pintype "bidirectional"))
      (node (ref "U10") (pin "9") (pinfunction "INT2/FSYNC/CLKIN_9") (pintype "unspecified"))
    )
    (net (code "89") (name "PC2-SPI2_MISO") (class "Default")
      (node (ref "R28") (pin "1") (pinfunction "1_1") (pintype "input"))
      (node (ref "U1") (pin "10") (pinfunction "PC2_10") (pintype "bidirectional"))
    )
    (net (code "90") (name "PC3-SPI2_MOSI") (class "Default")
      (node (ref "R27") (pin "1") (pinfunction "1_1") (pintype "input"))
      (node (ref "U1") (pin "11") (pinfunction "PC3_11") (pintype "bidirectional"))
    )
    (net (code "91") (name "PC4") (class "Default")
      (node (ref "H4") (pin "2") (pinfunction "2_2") (pintype "unspecified"))
      (node (ref "U1") (pin "24") (pinfunction "PC4_24") (pintype "bidirectional"))
    )
    (net (code "92") (name "PC5") (class "Default")
      (node (ref "H5") (pin "2") (pinfunction "2_2") (pintype "unspecified"))
      (node (ref "U1") (pin "25") (pinfunction "PC5_25") (pintype "bidirectional"))
    )
    (net (code "93") (name "PC6_KEY5") (class "Default")
      (node (ref "RN1") (pin "6") (pinfunction "6_6") (pintype "input"))
      (node (ref "SW2") (pin "6") (pinfunction "COMMON_6") (pintype "unspecified"))
      (node (ref "U1") (pin "37") (pinfunction "PC6_37") (pintype "bidirectional"))
    )
    (net (code "94") (name "PC7_KEY2") (class "Default")
      (node (ref "RN1") (pin "5") (pinfunction "5_5") (pintype "input"))
      (node (ref "SW2") (pin "3") (pinfunction "C_3") (pintype "unspecified"))
      (node (ref "U1") (pin "38") (pinfunction "PC7_38") (pintype "bidirectional"))
    )
    (net (code "95") (name "PC8_KEY1") (class "Default")
      (node (ref "R4") (pin "2") (pinfunction "2_2") (pintype "input"))
      (node (ref "SW2") (pin "2") (pinfunction "B_2") (pintype "unspecified"))
      (node (ref "U1") (pin "39") (pinfunction "PC8_39") (pintype "bidirectional"))
    )
    (net (code "96") (name "PC9_I2C3_SDA") (class "Default")
      (node (ref "U1") (pin "40") (pinfunction "PC9_40") (pintype "bidirectional"))
      (node (ref "U12") (pin "5") (pinfunction "5_5") (pintype "unspecified"))
    )
    (net (code "97") (name "PC10") (class "Default")
      (node (ref "R41") (pin "1") (pinfunction "1_1") (pintype "input"))
      (node (ref "U1") (pin "51") (pinfunction "PC10_51") (pintype "bidirectional"))
    )
    (net (code "98") (name "PC11") (class "Default")
      (node (ref "R42") (pin "1") (pinfunction "1_1") (pintype "input"))
      (node (ref "U1") (pin "52") (pinfunction "PC11_52") (pintype "bidirectional"))
    )
    (net (code "99") (name "PC12-UART5_TX") (class "Default")
      (node (ref "CN11") (pin "3") (pinfunction "3_3") (pintype "unspecified"))
      (node (ref "U1") (pin "53") (pinfunction "PC12_53") (pintype "bidirectional"))
    )
    (net (code "100") (name "PC13-CYL3") (class "Default")
      (node (ref "U1") (pin "2") (pinfunction "PC13_2") (pintype "bidirectional"))
      (node (ref "U8") (pin "3") (pinfunction "3B_3") (pintype "unspecified"))
    )
    (net (code "101") (name "PC14-CYL2") (class "Default")
      (node (ref "U1") (pin "3") (pinfunction "PC14-OSC32_IN(PC14)_3") (pintype "bidirectional"))
      (node (ref "U8") (pin "2") (pinfunction "2B_2") (pintype "unspecified"))
    )
    (net (code "102") (name "PC15-CYL1") (class "Default")
      (node (ref "U1") (pin "4") (pinfunction "PC15-OSC32_OUT(PC15)_4") (pintype "bidirectional"))
      (node (ref "U8") (pin "1") (pinfunction "1B_1") (pintype "unspecified"))
    )
    (net (code "103") (name "PD2-UART5_RX") (class "Default")
      (node (ref "CN11") (pin "4") (pinfunction "4_4") (pintype "unspecified"))
      (node (ref "U1") (pin "54") (pinfunction "PD2_54") (pintype "bidirectional"))
    )
    (net (code "104") (name "PH0-OSC_IN") (class "Default")
      (node (ref "C6") (pin "2") (pinfunction "2_2") (pintype "input"))
      (node (ref "U1") (pin "5") (pinfunction "PH0-OSC_IN(PH0)_5") (pintype "bidirectional"))
      (node (ref "X1") (pin "3") (pinfunction "OSC2_3") (pintype "unspecified"))
    )
    (net (code "105") (name "PH1-OSC_OUT") (class "Default")
      (node (ref "C7") (pin "2") (pinfunction "2_2") (pintype "input"))
      (node (ref "U1") (pin "6") (pinfunction "PH1-OSC_OUT(PH1)_6") (pintype "bidirectional"))
      (node (ref "X1") (pin "1") (pinfunction "OSC1_1") (pintype "unspecified"))
    )
    (net (code "106") (name "VIN") (class "Default")
      (node (ref "CN2") (pin "1") (pinfunction "1_1") (pintype "unspecified"))
      (node (ref "SW3") (pin "1") (pinfunction "1_1") (pintype "unspecified"))
    )
    (net (code "107") (name "VOUT") (class "Default")
      (node (ref "C13") (pin "2") (pinfunction "2_2") (pintype "input"))
      (node (ref "C14") (pin "2") (pinfunction "2_2") (pintype "input"))
      (node (ref "C27") (pin "1") (pinfunction "1_1") (pintype "input"))
      (node (ref "CN10") (pin "2") (pinfunction "2_2") (pintype "unspecified"))
      (node (ref "CN5") (pin "2") (pinfunction "2_2") (pintype "unspecified"))
      (node (ref "CN6") (pin "2") (pinfunction "2_2") (pintype "unspecified"))
      (node (ref "CN7") (pin "2") (pinfunction "2_2") (pintype "unspecified"))
      (node (ref "CN8") (pin "2") (pinfunction "2_2") (pintype "unspecified"))
      (node (ref "CN9") (pin "2") (pinfunction "2_2") (pintype "unspecified"))
      (node (ref "D1") (pin "1") (pinfunction "K_1") (pintype "input"))
      (node (ref "Q1") (pin "2") (pinfunction "S_2") (pintype "unspecified"))
      (node (ref "R14") (pin "1") (pinfunction "1_1") (pintype "input"))
      (node (ref "R19") (pin "1") (pinfunction "1_1") (pintype "input"))
      (node (ref "R20") (pin "1") (pinfunction "1_1") (pintype "input"))
      (node (ref "R21") (pin "1") (pinfunction "1_1") (pintype "input"))
      (node (ref "R22") (pin "1") (pinfunction "1_1") (pintype "input"))
      (node (ref "R23") (pin "1") (pinfunction "1_1") (pintype "input"))
      (node (ref "R24") (pin "1") (pinfunction "1_1") (pintype "input"))
      (node (ref "U4") (pin "7") (pinfunction "VIN_7") (pintype "unspecified"))
      (node (ref "U8") (pin "9") (pinfunction "COM_9") (pintype "unspecified"))
    )
    (net (code "108") (name "unconnected-(H2-Pad3)") (class "Default")
      (node (ref "H2") (pin "3") (pinfunction "3_3") (pintype "unspecified+no_connect"))
    )
    (net (code "109") (name "unconnected-(H2-Pad4)") (class "Default")
      (node (ref "H2") (pin "4") (pinfunction "4_4") (pintype "unspecified+no_connect"))
    )
    (net (code "110") (name "unconnected-(H2-Pad5)") (class "Default")
      (node (ref "H2") (pin "5") (pinfunction "5_5") (pintype "unspecified+no_connect"))
    )
    (net (code "111") (name "unconnected-(H2-Pad6)") (class "Default")
      (node (ref "H2") (pin "6") (pinfunction "6_6") (pintype "unspecified+no_connect"))
    )
    (net (code "112") (name "unconnected-(LED2-DOU-Pad2)") (class "Default")
      (node (ref "LED2") (pin "2") (pinfunction "DOU_2") (pintype "unspecified+no_connect"))
    )
    (net (code "113") (name "unconnected-(SCREW1-Pad1)") (class "Default")
      (node (ref "SCREW1") (pin "1") (pinfunction "1_1") (pintype "input+no_connect"))
    )
    (net (code "114") (name "unconnected-(SCREW2-Pad1)") (class "Default")
      (node (ref "SCREW2") (pin "1") (pinfunction "1_1") (pintype "input+no_connect"))
    )
    (net (code "115") (name "unconnected-(SCREW3-Pad1)") (class "Default")
      (node (ref "SCREW3") (pin "1") (pinfunction "1_1") (pintype "input+no_connect"))
    )
    (net (code "116") (name "unconnected-(SCREW4-Pad1)") (class "Default")
      (node (ref "SCREW4") (pin "1") (pinfunction "1_1") (pintype "input+no_connect"))
    )
    (net (code "117") (name "unconnected-(SW3-Pad3)") (class "Default")
      (node (ref "SW3") (pin "3") (pinfunction "3_3") (pintype "unspecified+no_connect"))
    )
    (net (code "118") (name "unconnected-(SW3-Pad4)") (class "Default")
      (node (ref "SW3") (pin "4") (pinfunction "4_4") (pintype "unspecified+no_connect"))
    )
    (net (code "119") (name "unconnected-(SW3-Pad5)") (class "Default")
      (node (ref "SW3") (pin "5") (pinfunction "5_5") (pintype "unspecified+no_connect"))
    )
    (net (code "120") (name "unconnected-(SW3-Pad6)") (class "Default")
      (node (ref "SW3") (pin "6") (pinfunction "6_6") (pintype "unspecified+no_connect"))
    )
    (net (code "121") (name "unconnected-(U4-ENA-Pad5)") (class "Default")
      (node (ref "U4") (pin "5") (pinfunction "ENA_5") (pintype "unspecified+no_connect"))
    )
    (net (code "122") (name "unconnected-(U4-NC-Pad2)") (class "Default")
      (node (ref "U4") (pin "2") (pinfunction "NC_2") (pintype "unspecified+no_connect"))
    )
    (net (code "123") (name "unconnected-(U4-NC-Pad3)") (class "Default")
      (node (ref "U4") (pin "3") (pinfunction "NC_3") (pintype "unspecified+no_connect"))
    )
    (net (code "124") (name "unconnected-(U6-SHDN-Pad5)") (class "Default")
      (node (ref "U6") (pin "5") (pinfunction "SHDN_5") (pintype "unspecified+no_connect"))
    )
    (net (code "125") (name "unconnected-(U7-SHDN-Pad5)") (class "Default")
      (node (ref "U7") (pin "5") (pinfunction "SHDN_5") (pintype "unspecified+no_connect"))
    )
    (net (code "126") (name "unconnected-(U8-7C-Pad10)") (class "Default")
      (node (ref "U8") (pin "10") (pinfunction "7C_10") (pintype "unspecified+no_connect"))
    )
    (net (code "127") (name "unconnected-(U10-RESV-Pad2)") (class "Default")
      (node (ref "U10") (pin "2") (pinfunction "RESV_2") (pintype "unspecified+no_connect"))
    )
    (net (code "128") (name "unconnected-(U10-RESV-Pad3)") (class "Default")
      (node (ref "U10") (pin "3") (pinfunction "RESV_3") (pintype "unspecified+no_connect"))
    )
    (net (code "129") (name "unconnected-(U10-RESV-Pad10)") (class "Default")
      (node (ref "U10") (pin "10") (pinfunction "RESV_10") (pintype "unspecified+no_connect"))
    )
    (net (code "130") (name "unconnected-(U10-RESV-Pad11)") (class "Default")
      (node (ref "U10") (pin "11") (pinfunction "RESV_11") (pintype "unspecified+no_connect"))
    )
  )
)
